# main_xml.net
KiCad netlist of a schematic drawn in EAGLE
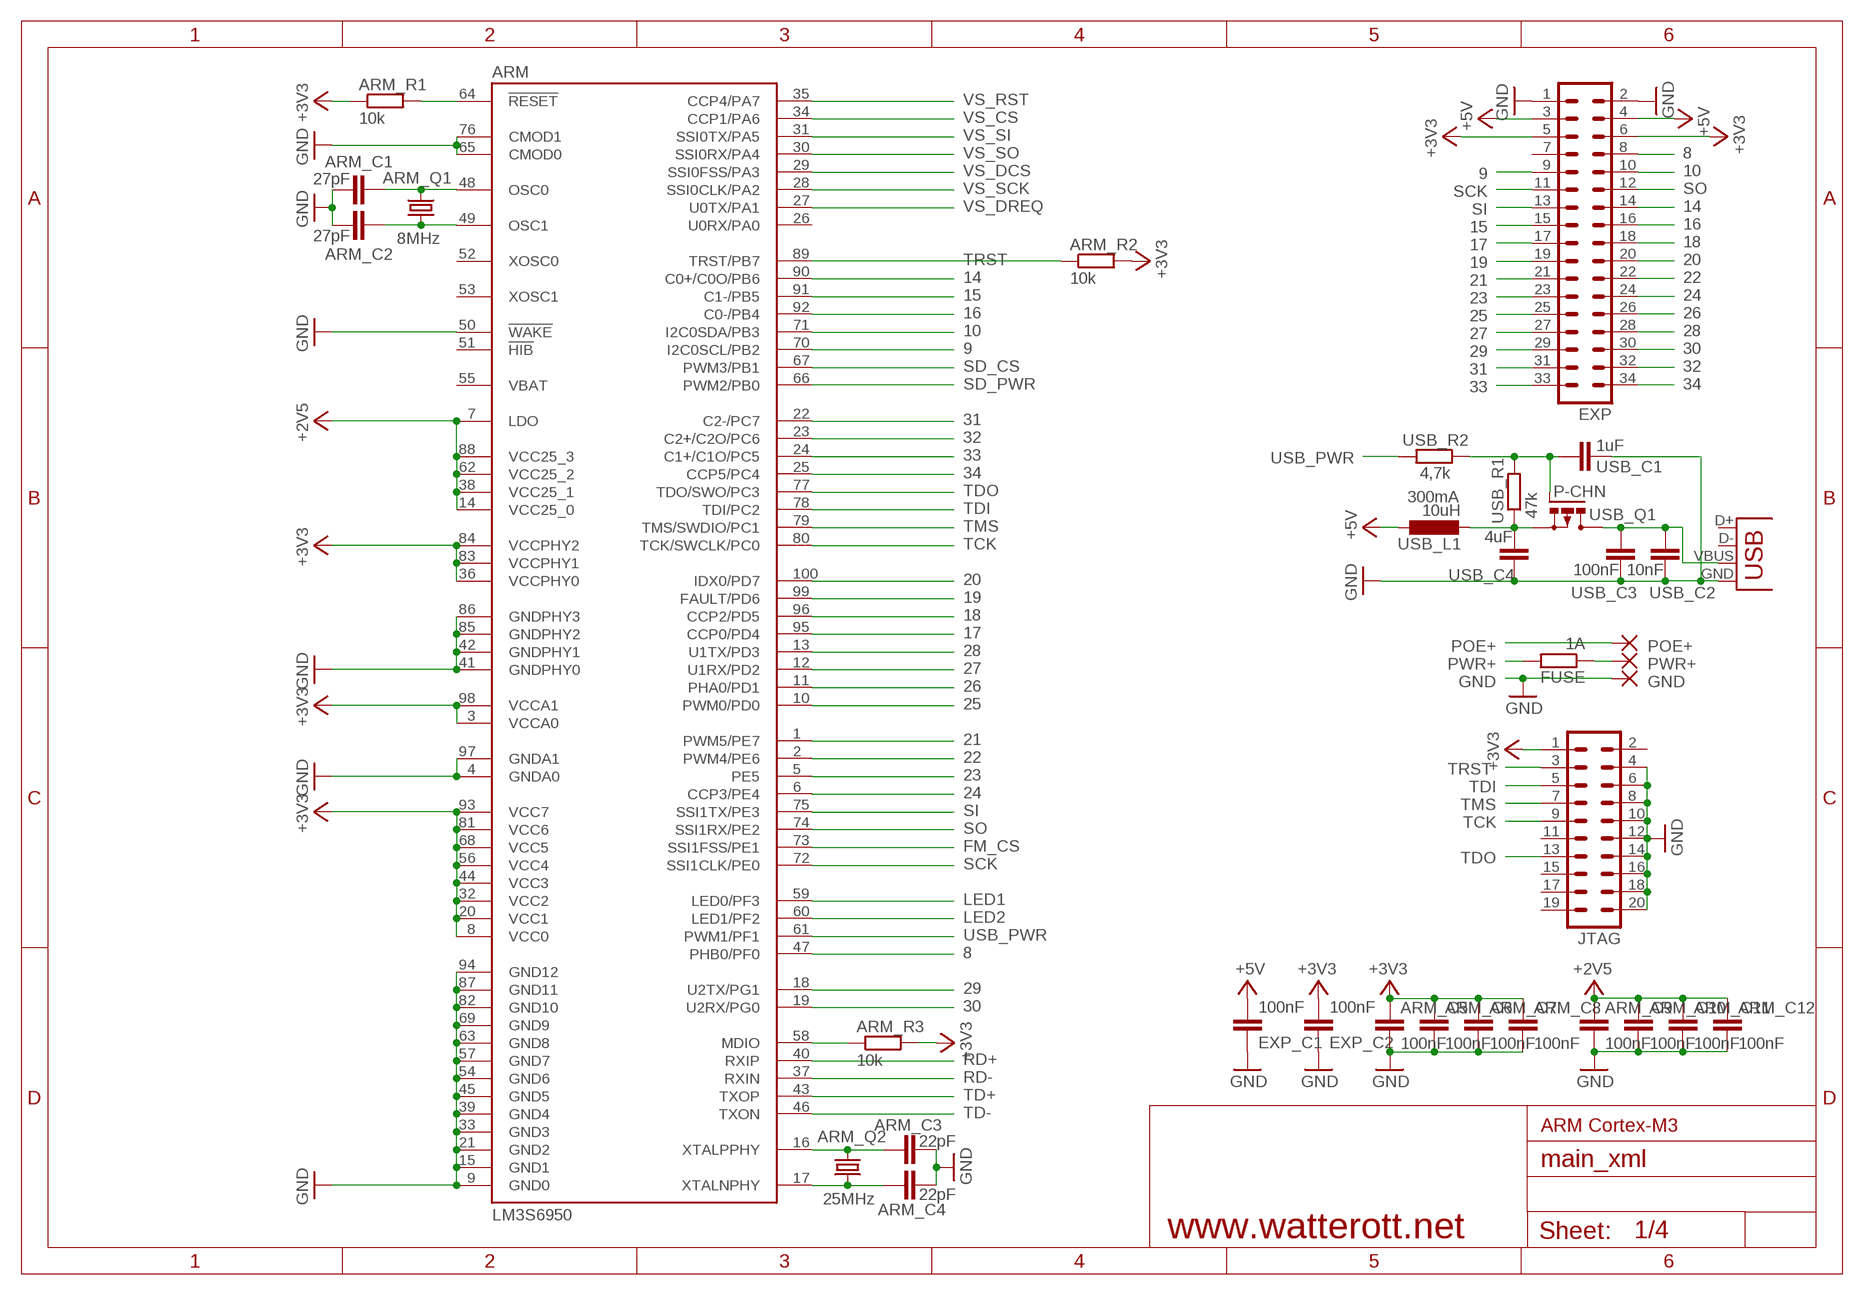
[diagram p0: schematic, sheet 1]
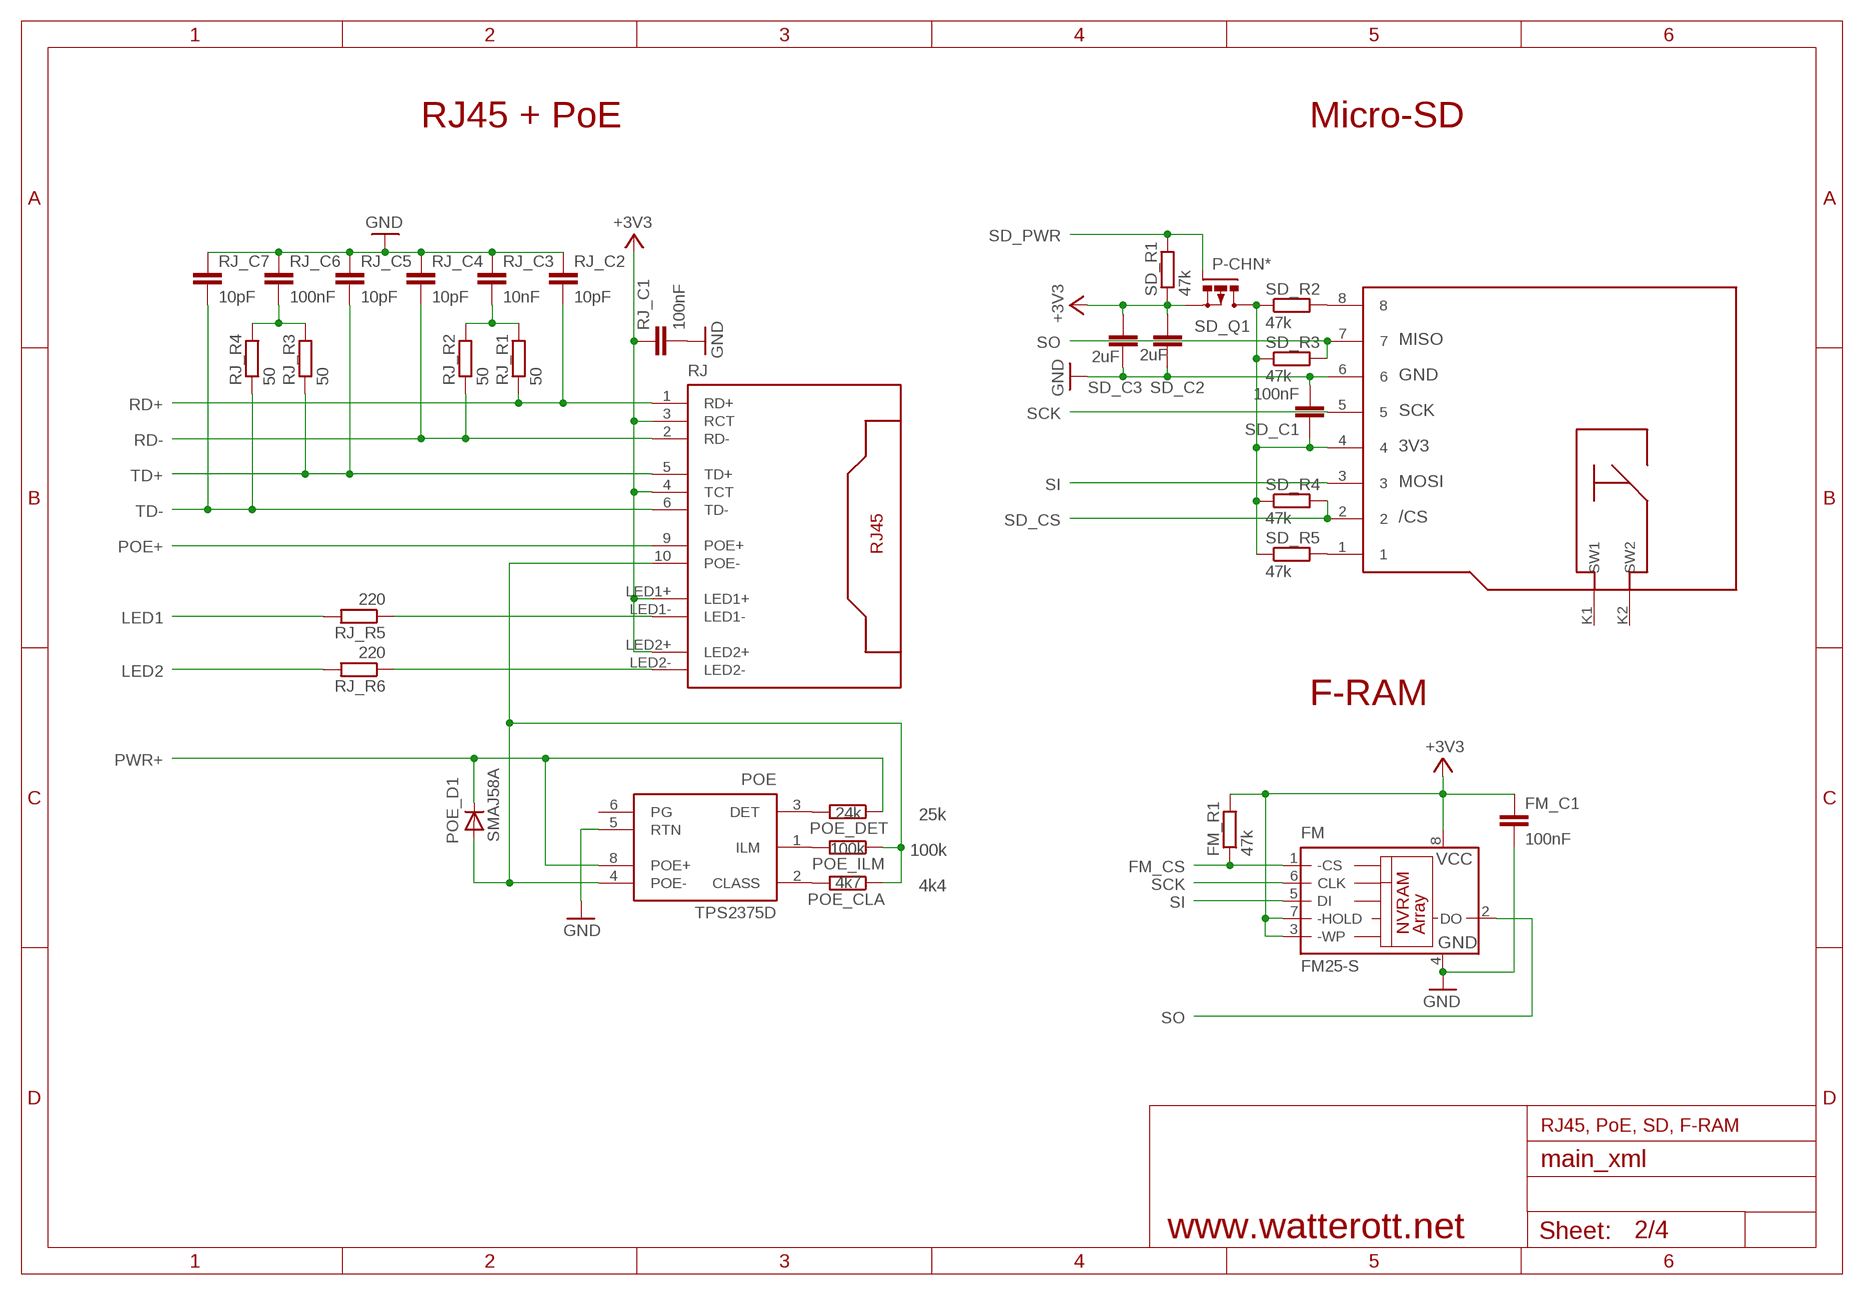
[diagram p1: schematic, sheet 2]
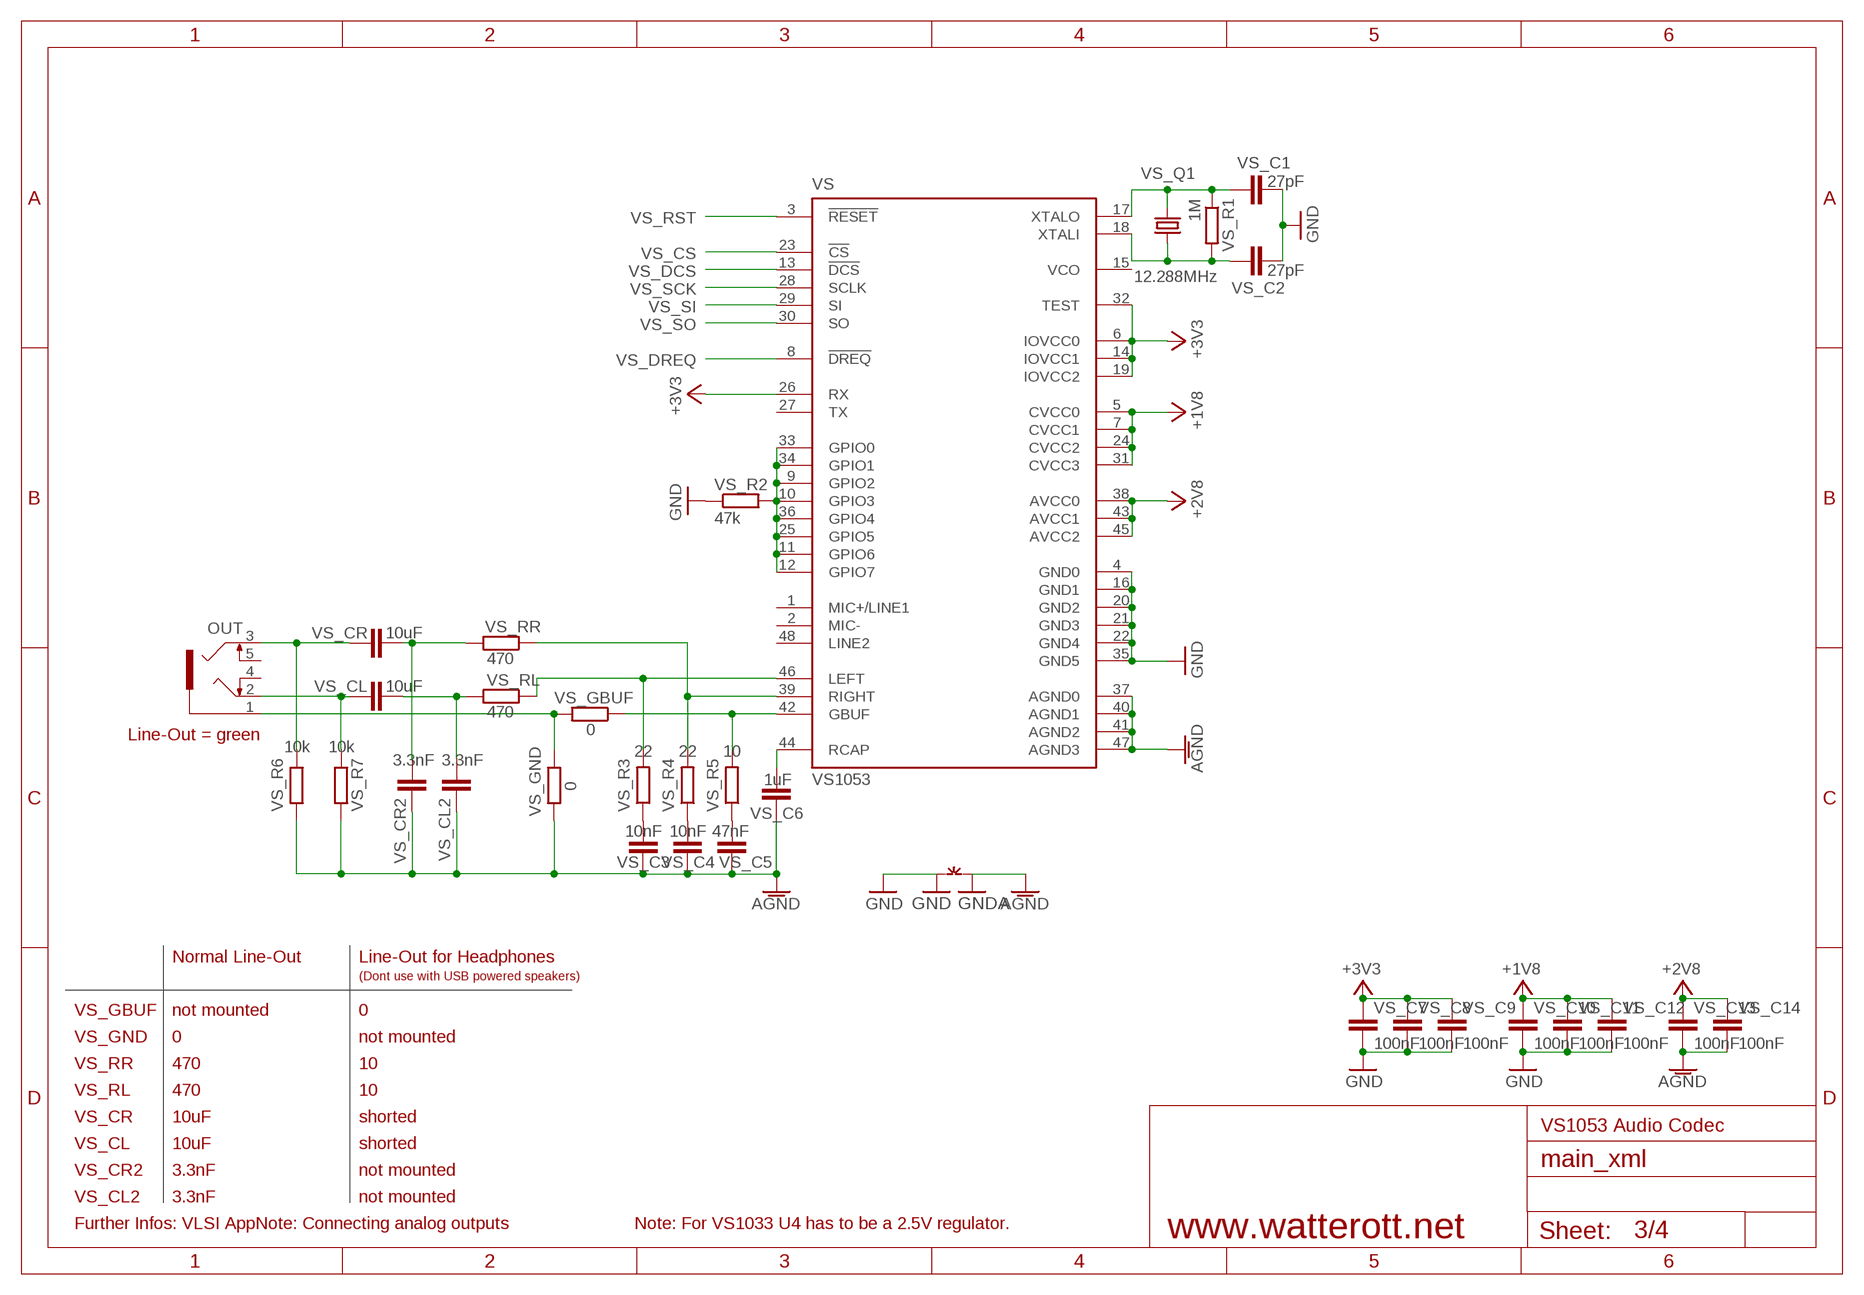
[diagram p2: schematic, sheet 3]
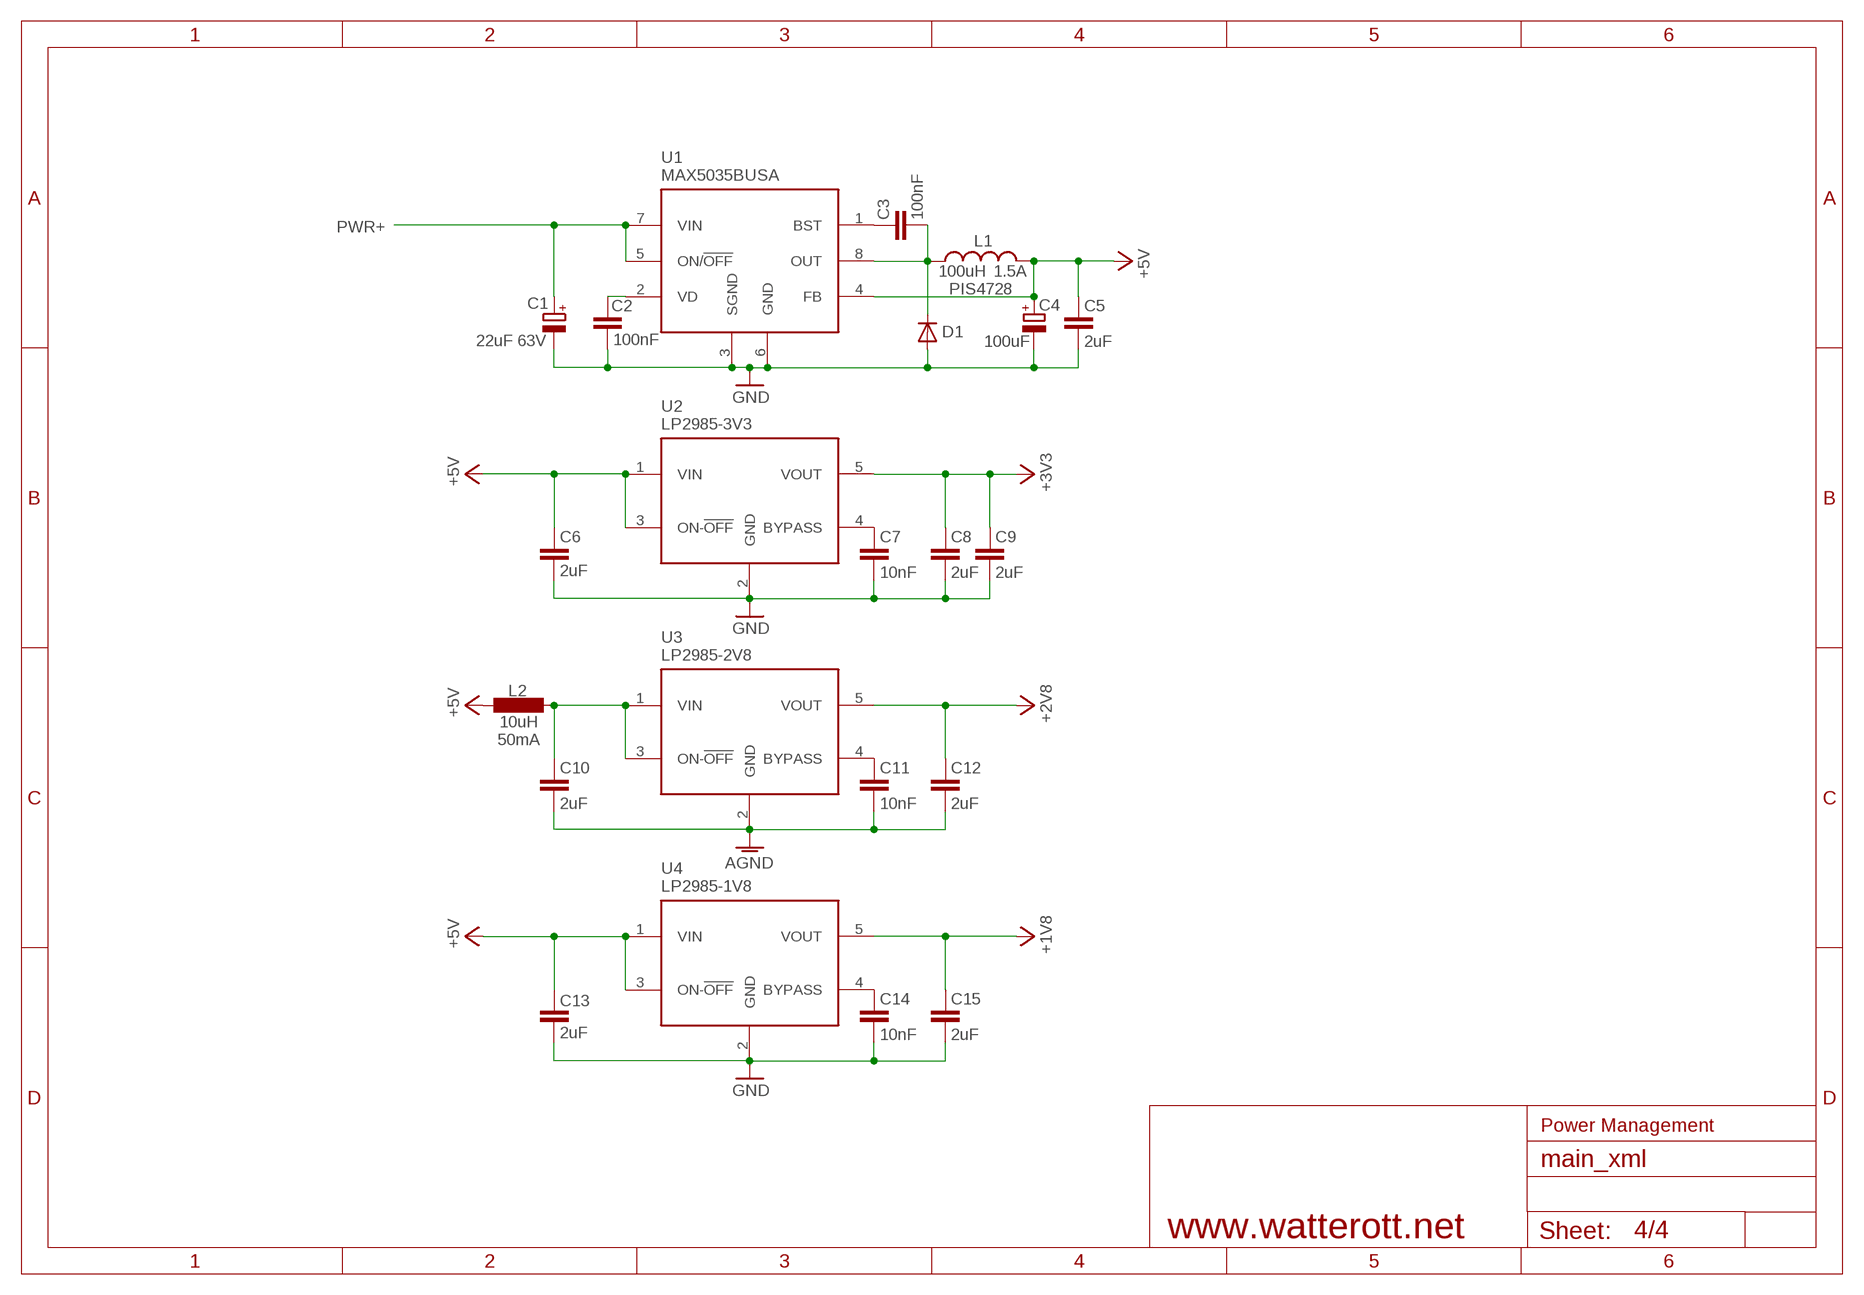
[diagram p3: schematic, sheet 4]

(export (version "E")
  (design (tool "Eeschema 10.0.6"))
  (components
    (comp (ref "FM")
      (value "FM25-S")
      (footprint "eagle-import:SO8")
      (libsource (lib "eagle-import") (part "FM25-S"))
    )
    (comp (ref "FM_C1")
      (value "100nF")
      (footprint "eagle-import:C0603")
      (libsource (lib "eagle-import") (part "C-EUC0603"))
    )
    (comp (ref "FM_R1")
      (value "47k")
      (footprint "eagle-import:R0603")
      (libsource (lib "eagle-import") (part "R-EU_R0603"))
    )
    (comp (ref "POE")
      (value "TPS2375D")
      (footprint "eagle-import:SO08")
      (libsource (lib "eagle-import") (part "TPS237X"))
    )
    (comp (ref "POE_CLA")
      (value "4k7")
      (footprint "eagle-import:R0603")
      (libsource (lib "eagle-import") (part "R-EU_R0603"))
    )
    (comp (ref "POE_D1")
      (value "SMAJ58A")
      (footprint "eagle-import:DO214AA")
      (libsource (lib "eagle-import") (part "DIODE-DO214AA"))
    )
    (comp (ref "POE_DET")
      (value "24k")
      (footprint "eagle-import:R0603")
      (libsource (lib "eagle-import") (part "R-EU_R0603"))
    )
    (comp (ref "POE_ILM")
      (value "100k")
      (footprint "eagle-import:R0603")
      (libsource (lib "eagle-import") (part "R-EU_R0603"))
    )
    (comp (ref "RJ")
      (value "RJ45-8-POEWE")
      (footprint "eagle-import:WE_POE")
      (libsource (lib "eagle-import") (part "RJ45-8-POEWE"))
    )
    (comp (ref "RJ_C1")
      (value "100nF")
      (footprint "eagle-import:C0603")
      (libsource (lib "eagle-import") (part "C-EUC0603"))
    )
    (comp (ref "RJ_C2")
      (value "10pF")
      (footprint "eagle-import:C0603")
      (libsource (lib "eagle-import") (part "C-EUC0603"))
    )
    (comp (ref "RJ_C3")
      (value "10nF")
      (footprint "eagle-import:C0603")
      (libsource (lib "eagle-import") (part "C-EUC0603"))
    )
    (comp (ref "RJ_C4")
      (value "10pF")
      (footprint "eagle-import:C0603")
      (libsource (lib "eagle-import") (part "C-EUC0603"))
    )
    (comp (ref "RJ_C5")
      (value "10pF")
      (footprint "eagle-import:C0603")
      (libsource (lib "eagle-import") (part "C-EUC0603"))
    )
    (comp (ref "RJ_C6")
      (value "100nF")
      (footprint "eagle-import:C0603")
      (libsource (lib "eagle-import") (part "C-EUC0603"))
    )
    (comp (ref "RJ_C7")
      (value "10pF")
      (footprint "eagle-import:C0603")
      (libsource (lib "eagle-import") (part "C-EUC0603"))
    )
    (comp (ref "RJ_R1")
      (value "50")
      (footprint "eagle-import:R0603")
      (libsource (lib "eagle-import") (part "R-EU_R0603"))
    )
    (comp (ref "RJ_R2")
      (value "50")
      (footprint "eagle-import:R0603")
      (libsource (lib "eagle-import") (part "R-EU_R0603"))
    )
    (comp (ref "RJ_R3")
      (value "50")
      (footprint "eagle-import:R0603")
      (libsource (lib "eagle-import") (part "R-EU_R0603"))
    )
    (comp (ref "RJ_R4")
      (value "50")
      (footprint "eagle-import:R0603")
      (libsource (lib "eagle-import") (part "R-EU_R0603"))
    )
    (comp (ref "RJ_R5")
      (value "220")
      (footprint "eagle-import:R0603")
      (libsource (lib "eagle-import") (part "R-EU_R0603"))
    )
    (comp (ref "RJ_R6")
      (value "220")
      (footprint "eagle-import:R0603")
      (libsource (lib "eagle-import") (part "R-EU_R0603"))
    )
    (comp (ref "SD")
      (value "MICRO-SD")
      (footprint "eagle-import:MICRO-SD")
      (libsource (lib "eagle-import") (part "MICRO-SD"))
    )
    (comp (ref "SD_C1")
      (value "100nF")
      (footprint "eagle-import:C0603")
      (libsource (lib "eagle-import") (part "C-EUC0603"))
    )
    (comp (ref "SD_C2")
      (value "2uF")
      (footprint "eagle-import:C0603")
      (libsource (lib "eagle-import") (part "C-EUC0603"))
    )
    (comp (ref "SD_C3")
      (value "2uF")
      (footprint "eagle-import:C0805")
      (libsource (lib "eagle-import") (part "C-EUC0805"))
    )
    (comp (ref "SD_Q1")
      (value "P-CHN*")
      (footprint "eagle-import:MICRO3")
      (libsource (lib "eagle-import") (part "IRLML6402"))
    )
    (comp (ref "SD_R1")
      (value "47k")
      (footprint "eagle-import:R0603")
      (libsource (lib "eagle-import") (part "R-EU_R0603"))
    )
    (comp (ref "SD_R2")
      (value "47k")
      (footprint "eagle-import:R0603")
      (libsource (lib "eagle-import") (part "R-EU_R0603"))
    )
    (comp (ref "SD_R3")
      (value "47k")
      (footprint "eagle-import:R0603")
      (libsource (lib "eagle-import") (part "R-EU_R0603"))
    )
    (comp (ref "SD_R4")
      (value "47k")
      (footprint "eagle-import:R0603")
      (libsource (lib "eagle-import") (part "R-EU_R0603"))
    )
    (comp (ref "SD_R5")
      (value "47k")
      (footprint "eagle-import:R0603")
      (libsource (lib "eagle-import") (part "R-EU_R0603"))
    )
    (comp (ref "ARM")
      (value "LM3S6950")
      (footprint "eagle-import:LQFP100")
      (libsource (lib "eagle-import") (part "LM3S6950"))
    )
    (comp (ref "ARM_C1")
      (value "27pF")
      (footprint "eagle-import:C0603")
      (libsource (lib "eagle-import") (part "C-EUC0603"))
    )
    (comp (ref "ARM_C2")
      (value "27pF")
      (footprint "eagle-import:C0603")
      (libsource (lib "eagle-import") (part "C-EUC0603"))
    )
    (comp (ref "ARM_C3")
      (value "22pF")
      (footprint "eagle-import:C0603")
      (libsource (lib "eagle-import") (part "C-EUC0603"))
    )
    (comp (ref "ARM_C4")
      (value "22pF")
      (footprint "eagle-import:C0603")
      (libsource (lib "eagle-import") (part "C-EUC0603"))
    )
    (comp (ref "ARM_C5")
      (value "100nF")
      (footprint "eagle-import:C0603")
      (libsource (lib "eagle-import") (part "C-EUC0603"))
    )
    (comp (ref "ARM_C6")
      (value "100nF")
      (footprint "eagle-import:C0603")
      (libsource (lib "eagle-import") (part "C-EUC0603"))
    )
    (comp (ref "ARM_C7")
      (value "100nF")
      (footprint "eagle-import:C0603")
      (libsource (lib "eagle-import") (part "C-EUC0603"))
    )
    (comp (ref "ARM_C8")
      (value "100nF")
      (footprint "eagle-import:C0603")
      (libsource (lib "eagle-import") (part "C-EUC0603"))
    )
    (comp (ref "ARM_C9")
      (value "100nF")
      (footprint "eagle-import:C0603")
      (libsource (lib "eagle-import") (part "C-EUC0603"))
    )
    (comp (ref "ARM_C10")
      (value "100nF")
      (footprint "eagle-import:C0603")
      (libsource (lib "eagle-import") (part "C-EUC0603"))
    )
    (comp (ref "ARM_C11")
      (value "100nF")
      (footprint "eagle-import:C0603")
      (libsource (lib "eagle-import") (part "C-EUC0603"))
    )
    (comp (ref "ARM_C12")
      (value "100nF")
      (footprint "eagle-import:C0603")
      (libsource (lib "eagle-import") (part "C-EUC0603"))
    )
    (comp (ref "ARM_Q1")
      (value "8MHz")
      (footprint "eagle-import:HC49UP")
      (libsource (lib "eagle-import") (part "HC49UP"))
    )
    (comp (ref "ARM_Q2")
      (value "25MHz")
      (footprint "eagle-import:HC49UP")
      (libsource (lib "eagle-import") (part "HC49UP"))
    )
    (comp (ref "ARM_R1")
      (value "10k")
      (footprint "eagle-import:R0603")
      (libsource (lib "eagle-import") (part "R-EU_R0603"))
    )
    (comp (ref "ARM_R2")
      (value "10k")
      (footprint "eagle-import:R0603")
      (libsource (lib "eagle-import") (part "R-EU_R0603"))
    )
    (comp (ref "ARM_R3")
      (value "10k")
      (footprint "eagle-import:R0603")
      (libsource (lib "eagle-import") (part "R-EU_R0603"))
    )
    (comp (ref "EXP")
      (value "MA17-2")
      (footprint "eagle-import:MA17-2")
      (libsource (lib "eagle-import") (part "MA17-2"))
    )
    (comp (ref "EXP_C1")
      (value "100nF")
      (footprint "eagle-import:C0603")
      (libsource (lib "eagle-import") (part "C-EUC0603"))
    )
    (comp (ref "EXP_C2")
      (value "100nF")
      (footprint "eagle-import:C0603")
      (libsource (lib "eagle-import") (part "C-EUC0603"))
    )
    (comp (ref "FUSE")
      (value "1A")
      (footprint "eagle-import:R1206")
      (libsource (lib "eagle-import") (part "R-EU_R1206"))
    )
    (comp (ref "GND")
      (value "SMD2")
      (footprint "eagle-import:SMD1,27-2,54")
      (libsource (lib "eagle-import") (part "SMD2"))
    )
    (comp (ref "JTAG")
      (value "MA10-2")
      (footprint "eagle-import:MA10-2")
      (libsource (lib "eagle-import") (part "MA10-2"))
    )
    (comp (ref "POE+")
      (value "SMD2")
      (footprint "eagle-import:SMD1,27-2,54")
      (libsource (lib "eagle-import") (part "SMD2"))
    )
    (comp (ref "PWR+")
      (value "SMD2")
      (footprint "eagle-import:SMD1,27-2,54")
      (libsource (lib "eagle-import") (part "SMD2"))
    )
    (comp (ref "USB")
      (value "USB-A-S")
      (footprint "eagle-import:USB-A-S")
      (libsource (lib "eagle-import") (part "USB-A-S"))
    )
    (comp (ref "USB_C1")
      (value "1uF")
      (footprint "eagle-import:C0603")
      (libsource (lib "eagle-import") (part "C-EUC0603"))
    )
    (comp (ref "USB_C2")
      (value "10nF")
      (footprint "eagle-import:C0603")
      (libsource (lib "eagle-import") (part "C-EUC0603"))
    )
    (comp (ref "USB_C3")
      (value "100nF")
      (footprint "eagle-import:C0603")
      (libsource (lib "eagle-import") (part "C-EUC0603"))
    )
    (comp (ref "USB_C4")
      (value "4uF")
      (footprint "eagle-import:C1206")
      (libsource (lib "eagle-import") (part "C-EUC1206"))
    )
    (comp (ref "USB_L1")
      (value "10uH")
      (footprint "eagle-import:L4532M")
      (libsource (lib "eagle-import") (part "L-EUL4532C"))
    )
    (comp (ref "USB_Q1")
      (value "P-CHN")
      (footprint "eagle-import:MICRO3")
      (libsource (lib "eagle-import") (part "IRLML6402"))
    )
    (comp (ref "USB_R1")
      (value "47k")
      (footprint "eagle-import:R0603")
      (libsource (lib "eagle-import") (part "R-EU_R0603"))
    )
    (comp (ref "USB_R2")
      (value "4,7k")
      (footprint "eagle-import:R0603")
      (libsource (lib "eagle-import") (part "R-EU_R0603"))
    )
    (comp (ref "C1")
      (value "22uF 63V")
      (footprint "eagle-import:153CLV-0810")
      (libsource (lib "eagle-import") (part "CPOL-EU153CLV-0810"))
    )
    (comp (ref "C2")
      (value "100nF")
      (footprint "eagle-import:C0603")
      (libsource (lib "eagle-import") (part "C-EUC0603"))
    )
    (comp (ref "C3")
      (value "100nF")
      (footprint "eagle-import:C0603")
      (libsource (lib "eagle-import") (part "C-EUC0603"))
    )
    (comp (ref "C4")
      (value "100uF")
      (footprint "eagle-import:153CLV-0810")
      (libsource (lib "eagle-import") (part "CPOL-EU153CLV-0810"))
    )
    (comp (ref "C5")
      (value "2uF")
      (footprint "eagle-import:C0603")
      (libsource (lib "eagle-import") (part "C-EUC0603"))
    )
    (comp (ref "C6")
      (value "2uF")
      (footprint "eagle-import:C0603")
      (libsource (lib "eagle-import") (part "C-EUC0603"))
    )
    (comp (ref "C7")
      (value "10nF")
      (footprint "eagle-import:C0603")
      (libsource (lib "eagle-import") (part "C-EUC0603"))
    )
    (comp (ref "C8")
      (value "2uF")
      (footprint "eagle-import:C0603")
      (libsource (lib "eagle-import") (part "C-EUC0603"))
    )
    (comp (ref "C9")
      (value "2uF")
      (footprint "eagle-import:C0603")
      (libsource (lib "eagle-import") (part "C-EUC0603"))
    )
    (comp (ref "C10")
      (value "2uF")
      (footprint "eagle-import:C0603")
      (libsource (lib "eagle-import") (part "C-EUC0603"))
    )
    (comp (ref "C11")
      (value "10nF")
      (footprint "eagle-import:C0603")
      (libsource (lib "eagle-import") (part "C-EUC0603"))
    )
    (comp (ref "C12")
      (value "2uF")
      (footprint "eagle-import:C0603")
      (libsource (lib "eagle-import") (part "C-EUC0603"))
    )
    (comp (ref "C13")
      (value "2uF")
      (footprint "eagle-import:C0603")
      (libsource (lib "eagle-import") (part "C-EUC0603"))
    )
    (comp (ref "C14")
      (value "10nF")
      (footprint "eagle-import:C0603")
      (libsource (lib "eagle-import") (part "C-EUC0603"))
    )
    (comp (ref "C15")
      (value "2uF")
      (footprint "eagle-import:C0603")
      (libsource (lib "eagle-import") (part "C-EUC0603"))
    )
    (comp (ref "D1")
      (value "Schottky 90V")
      (footprint "eagle-import:DO214AA")
      (libsource (lib "eagle-import") (part "DIODE-DO214AA"))
    )
    (comp (ref "L1")
      (value "100uH")
      (footprint "eagle-import:CDRH")
      (libsource (lib "eagle-import") (part "INDUCTORCDRH"))
    )
    (comp (ref "L2")
      (value "10uH")
      (footprint "eagle-import:L3216C")
      (libsource (lib "eagle-import") (part "L-EUL3216C"))
    )
    (comp (ref "U1")
      (value "MAX5035BUSA")
      (footprint "eagle-import:SO8")
      (libsource (lib "eagle-import") (part "MAX5035"))
    )
    (comp (ref "U2")
      (value "LP2985-3V3")
      (footprint "eagle-import:SOT23-5")
      (libsource (lib "eagle-import") (part "LP2985"))
    )
    (comp (ref "U3")
      (value "LP2985-2V8")
      (footprint "eagle-import:SOT23-5")
      (libsource (lib "eagle-import") (part "LP2985"))
    )
    (comp (ref "U4")
      (value "LP2985-1V8")
      (footprint "eagle-import:SOT23-5")
      (libsource (lib "eagle-import") (part "LP2985"))
    )
    (comp (ref "OUT")
      (value "1503_09")
      (footprint "eagle-import:1503_09")
      (libsource (lib "eagle-import") (part "1503_09"))
    )
    (comp (ref "VS")
      (value "VS1053")
      (footprint "eagle-import:LQFP-48")
      (libsource (lib "eagle-import") (part "VS1053"))
    )
    (comp (ref "VS_C1")
      (value "27pF")
      (footprint "eagle-import:C0603")
      (libsource (lib "eagle-import") (part "C-EUC0603"))
    )
    (comp (ref "VS_C2")
      (value "27pF")
      (footprint "eagle-import:C0603")
      (libsource (lib "eagle-import") (part "C-EUC0603"))
    )
    (comp (ref "VS_C3")
      (value "10nF")
      (footprint "eagle-import:C0603")
      (libsource (lib "eagle-import") (part "C-EUC0603"))
    )
    (comp (ref "VS_C4")
      (value "10nF")
      (footprint "eagle-import:C0603")
      (libsource (lib "eagle-import") (part "C-EUC0603"))
    )
    (comp (ref "VS_C5")
      (value "47nF")
      (footprint "eagle-import:C0603")
      (libsource (lib "eagle-import") (part "C-EUC0603"))
    )
    (comp (ref "VS_C6")
      (value "1uF")
      (footprint "eagle-import:C0603")
      (libsource (lib "eagle-import") (part "C-EUC0603"))
    )
    (comp (ref "VS_C7")
      (value "100nF")
      (footprint "eagle-import:C0603")
      (libsource (lib "eagle-import") (part "C-EUC0603"))
    )
    (comp (ref "VS_C8")
      (value "100nF")
      (footprint "eagle-import:C0603")
      (libsource (lib "eagle-import") (part "C-EUC0603"))
    )
    (comp (ref "VS_C9")
      (value "100nF")
      (footprint "eagle-import:C0603")
      (libsource (lib "eagle-import") (part "C-EUC0603"))
    )
    (comp (ref "VS_C10")
      (value "100nF")
      (footprint "eagle-import:C0603")
      (libsource (lib "eagle-import") (part "C-EUC0603"))
    )
    (comp (ref "VS_C11")
      (value "100nF")
      (footprint "eagle-import:C0603")
      (libsource (lib "eagle-import") (part "C-EUC0603"))
    )
    (comp (ref "VS_C12")
      (value "100nF")
      (footprint "eagle-import:C0603")
      (libsource (lib "eagle-import") (part "C-EUC0603"))
    )
    (comp (ref "VS_C13")
      (value "100nF")
      (footprint "eagle-import:C0603")
      (libsource (lib "eagle-import") (part "C-EUC0603"))
    )
    (comp (ref "VS_C14")
      (value "100nF")
      (footprint "eagle-import:C0603")
      (libsource (lib "eagle-import") (part "C-EUC0603"))
    )
    (comp (ref "VS_CL")
      (value "10uF")
      (footprint "eagle-import:C1812")
      (libsource (lib "eagle-import") (part "C-EUC1812"))
    )
    (comp (ref "VS_CL2")
      (value "3.3nF")
      (footprint "eagle-import:C0603")
      (libsource (lib "eagle-import") (part "C-EUC0603"))
    )
    (comp (ref "VS_CR")
      (value "10uF")
      (footprint "eagle-import:C1812")
      (libsource (lib "eagle-import") (part "C-EUC1812"))
    )
    (comp (ref "VS_CR2")
      (value "3.3nF")
      (footprint "eagle-import:C0603")
      (libsource (lib "eagle-import") (part "C-EUC0603"))
    )
    (comp (ref "VS_GBUF")
      (value "0")
      (footprint "eagle-import:R0603")
      (libsource (lib "eagle-import") (part "R-EU_R0603"))
    )
    (comp (ref "VS_GND")
      (value "0")
      (footprint "eagle-import:R0603")
      (libsource (lib "eagle-import") (part "R-EU_R0603"))
    )
    (comp (ref "VS_Q1")
      (value "12.288MHz")
      (footprint "eagle-import:HC49UP")
      (libsource (lib "eagle-import") (part "HC49UP"))
    )
    (comp (ref "VS_R1")
      (value "1M")
      (footprint "eagle-import:R0603")
      (libsource (lib "eagle-import") (part "R-EU_R0603"))
    )
    (comp (ref "VS_R2")
      (value "47k")
      (footprint "eagle-import:R0603")
      (libsource (lib "eagle-import") (part "R-EU_R0603"))
    )
    (comp (ref "VS_R3")
      (value "22")
      (footprint "eagle-import:R0603")
      (libsource (lib "eagle-import") (part "R-EU_R0603"))
    )
    (comp (ref "VS_R4")
      (value "22")
      (footprint "eagle-import:R0603")
      (libsource (lib "eagle-import") (part "R-EU_R0603"))
    )
    (comp (ref "VS_R5")
      (value "10")
      (footprint "eagle-import:R0603")
      (libsource (lib "eagle-import") (part "R-EU_R0603"))
    )
    (comp (ref "VS_R6")
      (value "10k")
      (footprint "eagle-import:R0603")
      (libsource (lib "eagle-import") (part "R-EU_R0603"))
    )
    (comp (ref "VS_R7")
      (value "10k")
      (footprint "eagle-import:R0603")
      (libsource (lib "eagle-import") (part "R-EU_R0603"))
    )
    (comp (ref "VS_RL")
      (value "470")
      (footprint "eagle-import:R0603")
      (libsource (lib "eagle-import") (part "R-EU_R0603"))
    )
    (comp (ref "VS_RR")
      (value "470")
      (footprint "eagle-import:R0603")
      (libsource (lib "eagle-import") (part "R-EU_R0603"))
    )
    (comp (ref "~NUDEV~1")
      (value "GND-GNDA")
      (footprint "eagle-import:GND-GNDA")
      (libsource (lib "eagle-import") (part "GND-GNDA"))
    )
  )
  (nets
    (net (code "1") (name "+1V8") (class "Default")
      (node (ref "C15") (pin "1") (pinfunction "1_1") (pintype "passive"))
      (node (ref "U4") (pin "5") (pinfunction "VOUT_5") (pintype "power_in"))
      (node (ref "VS") (pin "24") (pinfunction "CVCC2_24") (pintype "power_in"))
      (node (ref "VS") (pin "31") (pinfunction "CVCC3_31") (pintype "power_in"))
      (node (ref "VS") (pin "5") (pinfunction "CVCC0_5") (pintype "power_in"))
      (node (ref "VS") (pin "7") (pinfunction "CVCC1_7") (pintype "power_in"))
      (node (ref "VS_C10") (pin "1") (pinfunction "1_1") (pintype "passive"))
      (node (ref "VS_C11") (pin "1") (pinfunction "1_1") (pintype "passive"))
      (node (ref "VS_C12") (pin "1") (pinfunction "1_1") (pintype "passive"))
    )
    (net (code "2") (name "+2V8") (class "Default")
      (node (ref "C12") (pin "1") (pinfunction "1_1") (pintype "passive"))
      (node (ref "U3") (pin "5") (pinfunction "VOUT_5") (pintype "power_in"))
      (node (ref "VS") (pin "38") (pinfunction "AVCC0_38") (pintype "power_in"))
      (node (ref "VS") (pin "43") (pinfunction "AVCC1_43") (pintype "power_in"))
      (node (ref "VS") (pin "45") (pinfunction "AVCC2_45") (pintype "power_in"))
      (node (ref "VS_C13") (pin "1") (pinfunction "1_1") (pintype "passive"))
      (node (ref "VS_C14") (pin "1") (pinfunction "1_1") (pintype "passive"))
    )
    (net (code "3") (name "+3V3") (class "Default")
      (node (ref "ARM") (pin "20") (pinfunction "VCC1_20") (pintype "power_in"))
      (node (ref "ARM") (pin "3") (pinfunction "VCCA0_3") (pintype "power_in"))
      (node (ref "ARM") (pin "32") (pinfunction "VCC2_32") (pintype "power_in"))
      (node (ref "ARM") (pin "36") (pinfunction "VCCPHY0_36") (pintype "power_in"))
      (node (ref "ARM") (pin "44") (pinfunction "VCC3_44") (pintype "power_in"))
      (node (ref "ARM") (pin "56") (pinfunction "VCC4_56") (pintype "power_in"))
      (node (ref "ARM") (pin "68") (pinfunction "VCC5_68") (pintype "power_in"))
      (node (ref "ARM") (pin "8") (pinfunction "VCC0_8") (pintype "power_in"))
      (node (ref "ARM") (pin "81") (pinfunction "VCC6_81") (pintype "power_in"))
      (node (ref "ARM") (pin "83") (pinfunction "VCCPHY1_83") (pintype "power_in"))
      (node (ref "ARM") (pin "84") (pinfunction "VCCPHY2_84") (pintype "power_in"))
      (node (ref "ARM") (pin "93") (pinfunction "VCC7_93") (pintype "power_in"))
      (node (ref "ARM") (pin "98") (pinfunction "VCCA1_98") (pintype "power_in"))
      (node (ref "ARM_C5") (pin "1") (pinfunction "1_1") (pintype "passive"))
      (node (ref "ARM_C6") (pin "1") (pinfunction "1_1") (pintype "passive"))
      (node (ref "ARM_C7") (pin "1") (pinfunction "1_1") (pintype "passive"))
      (node (ref "ARM_C8") (pin "1") (pinfunction "1_1") (pintype "passive"))
      (node (ref "ARM_R1") (pin "1") (pinfunction "1_1") (pintype "passive"))
      (node (ref "ARM_R2") (pin "2") (pinfunction "2_2") (pintype "passive"))
      (node (ref "ARM_R3") (pin "2") (pinfunction "2_2") (pintype "passive"))
      (node (ref "C8") (pin "1") (pinfunction "1_1") (pintype "passive"))
      (node (ref "C9") (pin "1") (pinfunction "1_1") (pintype "passive"))
      (node (ref "EXP") (pin "5") (pinfunction "5_5") (pintype "passive"))
      (node (ref "EXP") (pin "6") (pinfunction "6_6") (pintype "passive"))
      (node (ref "EXP_C2") (pin "2") (pinfunction "2_2") (pintype "passive"))
      (node (ref "FM") (pin "3") (pinfunction "-WP_3") (pintype "input"))
      (node (ref "FM") (pin "7") (pinfunction "-HOLD_7") (pintype "input"))
      (node (ref "FM") (pin "8") (pinfunction "VCC_8") (pintype "power_in"))
      (node (ref "FM_C1") (pin "1") (pinfunction "1_1") (pintype "passive"))
      (node (ref "FM_R1") (pin "2") (pinfunction "2_2") (pintype "passive"))
      (node (ref "JTAG") (pin "1") (pinfunction "1_1") (pintype "passive"))
      (node (ref "RJ") (pin "3") (pinfunction "RCT_3") (pintype "bidirectional"))
      (node (ref "RJ") (pin "4") (pinfunction "TCT_4") (pintype "bidirectional"))
      (node (ref "RJ") (pin "LED1+") (pinfunction "LED1+_LED1+") (pintype "input"))
      (node (ref "RJ") (pin "LED2+") (pinfunction "LED2+_LED2+") (pintype "input"))
      (node (ref "RJ_C1") (pin "1") (pinfunction "1_1") (pintype "passive"))
      (node (ref "SD_C2") (pin "2") (pinfunction "2_2") (pintype "passive"))
      (node (ref "SD_C3") (pin "2") (pinfunction "2_2") (pintype "passive"))
      (node (ref "SD_Q1") (pin "2") (pinfunction "S_2") (pintype "passive"))
      (node (ref "SD_R1") (pin "1") (pinfunction "1_1") (pintype "passive"))
      (node (ref "U2") (pin "5") (pinfunction "VOUT_5") (pintype "power_in"))
      (node (ref "VS") (pin "14") (pinfunction "IOVCC1_14") (pintype "power_in"))
      (node (ref "VS") (pin "19") (pinfunction "IOVCC2_19") (pintype "power_in"))
      (node (ref "VS") (pin "26") (pinfunction "RX_26") (pintype "input"))
      (node (ref "VS") (pin "32") (pinfunction "TEST_32") (pintype "input"))
      (node (ref "VS") (pin "6") (pinfunction "IOVCC0_6") (pintype "power_in"))
      (node (ref "VS_C7") (pin "1") (pinfunction "1_1") (pintype "passive"))
      (node (ref "VS_C8") (pin "1") (pinfunction "1_1") (pintype "passive"))
      (node (ref "VS_C9") (pin "1") (pinfunction "1_1") (pintype "passive"))
    )
    (net (code "4") (name "+5V") (class "Default")
      (node (ref "C13") (pin "2") (pinfunction "2_2") (pintype "passive"))
      (node (ref "C4") (pin "+") (pinfunction "+_+") (pintype "passive"))
      (node (ref "C5") (pin "1") (pinfunction "1_1") (pintype "passive"))
      (node (ref "C6") (pin "2") (pinfunction "2_2") (pintype "passive"))
      (node (ref "EXP") (pin "3") (pinfunction "3_3") (pintype "passive"))
      (node (ref "EXP") (pin "4") (pinfunction "4_4") (pintype "passive"))
      (node (ref "EXP_C1") (pin "2") (pinfunction "2_2") (pintype "passive"))
      (node (ref "L1") (pin "2") (pinfunction "2_2") (pintype "passive"))
      (node (ref "L2") (pin "1") (pinfunction "1_1") (pintype "passive"))
      (node (ref "U1") (pin "4") (pinfunction "FB_4") (pintype "input"))
      (node (ref "U2") (pin "1") (pinfunction "VIN_1") (pintype "power_in"))
      (node (ref "U2") (pin "3") (pinfunction "ON-~{OFF}_3") (pintype "input"))
      (node (ref "U4") (pin "1") (pinfunction "VIN_1") (pintype "power_in"))
      (node (ref "U4") (pin "3") (pinfunction "ON-~{OFF}_3") (pintype "input"))
      (node (ref "USB_L1") (pin "1") (pinfunction "1_1") (pintype "passive"))
    )
    (net (code "5") (name "8") (class "Default")
      (node (ref "ARM") (pin "47") (pinfunction "PHB0/PF0_47") (pintype "bidirectional"))
      (node (ref "EXP") (pin "8") (pinfunction "8_8") (pintype "passive"))
    )
    (net (code "6") (name "9") (class "Default")
      (node (ref "ARM") (pin "70") (pinfunction "I2C0SCL/PB2_70") (pintype "bidirectional"))
      (node (ref "EXP") (pin "9") (pinfunction "9_9") (pintype "passive"))
    )
    (net (code "7") (name "10") (class "Default")
      (node (ref "ARM") (pin "71") (pinfunction "I2C0SDA/PB3_71") (pintype "bidirectional"))
      (node (ref "EXP") (pin "10") (pinfunction "10_10") (pintype "passive"))
    )
    (net (code "8") (name "14") (class "Default")
      (node (ref "ARM") (pin "90") (pinfunction "C0+/C0O/PB6_90") (pintype "bidirectional"))
      (node (ref "EXP") (pin "14") (pinfunction "14_14") (pintype "passive"))
    )
    (net (code "9") (name "15") (class "Default")
      (node (ref "ARM") (pin "91") (pinfunction "C1-/PB5_91") (pintype "bidirectional"))
      (node (ref "EXP") (pin "15") (pinfunction "15_15") (pintype "passive"))
    )
    (net (code "10") (name "16") (class "Default")
      (node (ref "ARM") (pin "92") (pinfunction "C0-/PB4_92") (pintype "bidirectional"))
      (node (ref "EXP") (pin "16") (pinfunction "16_16") (pintype "passive"))
    )
    (net (code "11") (name "17") (class "Default")
      (node (ref "ARM") (pin "95") (pinfunction "CCP0/PD4_95") (pintype "bidirectional"))
      (node (ref "EXP") (pin "17") (pinfunction "17_17") (pintype "passive"))
    )
    (net (code "12") (name "18") (class "Default")
      (node (ref "ARM") (pin "96") (pinfunction "CCP2/PD5_96") (pintype "bidirectional"))
      (node (ref "EXP") (pin "18") (pinfunction "18_18") (pintype "passive"))
    )
    (net (code "13") (name "19") (class "Default")
      (node (ref "ARM") (pin "99") (pinfunction "FAULT/PD6_99") (pintype "bidirectional"))
      (node (ref "EXP") (pin "19") (pinfunction "19_19") (pintype "passive"))
    )
    (net (code "14") (name "20") (class "Default")
      (node (ref "ARM") (pin "100") (pinfunction "IDX0/PD7_100") (pintype "bidirectional"))
      (node (ref "EXP") (pin "20") (pinfunction "20_20") (pintype "passive"))
    )
    (net (code "15") (name "21") (class "Default")
      (node (ref "ARM") (pin "1") (pinfunction "PWM5/PE7_1") (pintype "bidirectional"))
      (node (ref "EXP") (pin "21") (pinfunction "21_21") (pintype "passive"))
    )
    (net (code "16") (name "22") (class "Default")
      (node (ref "ARM") (pin "2") (pinfunction "PWM4/PE6_2") (pintype "bidirectional"))
      (node (ref "EXP") (pin "22") (pinfunction "22_22") (pintype "passive"))
    )
    (net (code "17") (name "23") (class "Default")
      (node (ref "ARM") (pin "5") (pinfunction "PE5_5") (pintype "bidirectional"))
      (node (ref "EXP") (pin "23") (pinfunction "23_23") (pintype "passive"))
    )
    (net (code "18") (name "24") (class "Default")
      (node (ref "ARM") (pin "6") (pinfunction "CCP3/PE4_6") (pintype "bidirectional"))
      (node (ref "EXP") (pin "24") (pinfunction "24_24") (pintype "passive"))
    )
    (net (code "19") (name "25") (class "Default")
      (node (ref "ARM") (pin "10") (pinfunction "PWM0/PD0_10") (pintype "bidirectional"))
      (node (ref "EXP") (pin "25") (pinfunction "25_25") (pintype "passive"))
    )
    (net (code "20") (name "26") (class "Default")
      (node (ref "ARM") (pin "11") (pinfunction "PHA0/PD1_11") (pintype "bidirectional"))
      (node (ref "EXP") (pin "26") (pinfunction "26_26") (pintype "passive"))
    )
    (net (code "21") (name "27") (class "Default")
      (node (ref "ARM") (pin "12") (pinfunction "U1RX/PD2_12") (pintype "bidirectional"))
      (node (ref "EXP") (pin "27") (pinfunction "27_27") (pintype "passive"))
    )
    (net (code "22") (name "28") (class "Default")
      (node (ref "ARM") (pin "13") (pinfunction "U1TX/PD3_13") (pintype "bidirectional"))
      (node (ref "EXP") (pin "28") (pinfunction "28_28") (pintype "passive"))
    )
    (net (code "23") (name "29") (class "Default")
      (node (ref "ARM") (pin "18") (pinfunction "U2TX/PG1_18") (pintype "bidirectional"))
      (node (ref "EXP") (pin "29") (pinfunction "29_29") (pintype "passive"))
    )
    (net (code "24") (name "30") (class "Default")
      (node (ref "ARM") (pin "19") (pinfunction "U2RX/PG0_19") (pintype "bidirectional"))
      (node (ref "EXP") (pin "30") (pinfunction "30_30") (pintype "passive"))
    )
    (net (code "25") (name "31") (class "Default")
      (node (ref "ARM") (pin "22") (pinfunction "C2-/PC7_22") (pintype "bidirectional"))
      (node (ref "EXP") (pin "31") (pinfunction "31_31") (pintype "passive"))
    )
    (net (code "26") (name "32") (class "Default")
      (node (ref "ARM") (pin "23") (pinfunction "C2+/C2O/PC6_23") (pintype "bidirectional"))
      (node (ref "EXP") (pin "32") (pinfunction "32_32") (pintype "passive"))
    )
    (net (code "27") (name "33") (class "Default")
      (node (ref "ARM") (pin "24") (pinfunction "C1+/C1O/PC5_24") (pintype "bidirectional"))
      (node (ref "EXP") (pin "33") (pinfunction "33_33") (pintype "passive"))
    )
    (net (code "28") (name "34") (class "Default")
      (node (ref "ARM") (pin "25") (pinfunction "CCP5/PC4_25") (pintype "bidirectional"))
      (node (ref "EXP") (pin "34") (pinfunction "34_34") (pintype "passive"))
    )
    (net (code "29") (name "AGND") (class "Default")
      (node (ref "C10") (pin "1") (pinfunction "1_1") (pintype "passive"))
      (node (ref "C11") (pin "2") (pinfunction "2_2") (pintype "passive"))
      (node (ref "C12") (pin "2") (pinfunction "2_2") (pintype "passive"))
      (node (ref "U3") (pin "2") (pinfunction "GND_2") (pintype "power_in"))
      (node (ref "VS") (pin "37") (pinfunction "AGND0_37") (pintype "power_in"))
      (node (ref "VS") (pin "40") (pinfunction "AGND1_40") (pintype "power_in"))
      (node (ref "VS") (pin "41") (pinfunction "AGND2_41") (pintype "power_in"))
      (node (ref "VS") (pin "47") (pinfunction "AGND3_47") (pintype "power_in"))
      (node (ref "VS_C13") (pin "2") (pinfunction "2_2") (pintype "passive"))
      (node (ref "VS_C14") (pin "2") (pinfunction "2_2") (pintype "passive"))
      (node (ref "VS_C3") (pin "1") (pinfunction "1_1") (pintype "passive"))
      (node (ref "VS_C4") (pin "1") (pinfunction "1_1") (pintype "passive"))
      (node (ref "VS_C5") (pin "1") (pinfunction "1_1") (pintype "passive"))
      (node (ref "VS_C6") (pin "1") (pinfunction "1_1") (pintype "passive"))
      (node (ref "VS_CL2") (pin "2") (pinfunction "2_2") (pintype "passive"))
      (node (ref "VS_CR2") (pin "2") (pinfunction "2_2") (pintype "passive"))
      (node (ref "VS_GND") (pin "2") (pinfunction "2_2") (pintype "passive"))
      (node (ref "VS_R6") (pin "2") (pinfunction "2_2") (pintype "passive"))
      (node (ref "VS_R7") (pin "2") (pinfunction "2_2") (pintype "passive"))
      (node (ref "~NUDEV~1") (pin "GNDA") (pinfunction "GNDA_GNDA") (pintype "power_in"))
    )
    (net (code "30") (name "FM_CS") (class "Default")
      (node (ref "ARM") (pin "73") (pinfunction "SSI1FSS/PE1_73") (pintype "bidirectional"))
      (node (ref "FM") (pin "1") (pinfunction "-CS_1") (pintype "input"))
      (node (ref "FM_R1") (pin "1") (pinfunction "1_1") (pintype "passive"))
    )
    (net (code "31") (name "GND") (class "Default")
      (node (ref "ARM") (pin "15") (pinfunction "GND1_15") (pintype "power_in"))
      (node (ref "ARM") (pin "21") (pinfunction "GND2_21") (pintype "power_in"))
      (node (ref "ARM") (pin "33") (pinfunction "GND3_33") (pintype "power_in"))
      (node (ref "ARM") (pin "39") (pinfunction "GND4_39") (pintype "power_in"))
      (node (ref "ARM") (pin "4") (pinfunction "GNDA0_4") (pintype "power_in"))
      (node (ref "ARM") (pin "41") (pinfunction "GNDPHY0_41") (pintype "power_in"))
      (node (ref "ARM") (pin "42") (pinfunction "GNDPHY1_42") (pintype "power_in"))
      (node (ref "ARM") (pin "45") (pinfunction "GND5_45") (pintype "power_in"))
      (node (ref "ARM") (pin "50") (pinfunction "~{WAKE}_50") (pintype "input"))
      (node (ref "ARM") (pin "54") (pinfunction "GND6_54") (pintype "power_in"))
      (node (ref "ARM") (pin "57") (pinfunction "GND7_57") (pintype "power_in"))
      (node (ref "ARM") (pin "63") (pinfunction "GND8_63") (pintype "power_in"))
      (node (ref "ARM") (pin "65") (pinfunction "CMOD0_65") (pintype "bidirectional"))
      (node (ref "ARM") (pin "69") (pinfunction "GND9_69") (pintype "power_in"))
      (node (ref "ARM") (pin "76") (pinfunction "CMOD1_76") (pintype "bidirectional"))
      (node (ref "ARM") (pin "82") (pinfunction "GND10_82") (pintype "power_in"))
      (node (ref "ARM") (pin "85") (pinfunction "GNDPHY2_85") (pintype "power_in"))
      (node (ref "ARM") (pin "86") (pinfunction "GNDPHY3_86") (pintype "power_in"))
      (node (ref "ARM") (pin "87") (pinfunction "GND11_87") (pintype "power_in"))
      (node (ref "ARM") (pin "9") (pinfunction "GND0_9") (pintype "power_in"))
      (node (ref "ARM") (pin "94") (pinfunction "GND12_94") (pintype "power_in"))
      (node (ref "ARM") (pin "97") (pinfunction "GNDA1_97") (pintype "power_in"))
      (node (ref "ARM_C1") (pin "2") (pinfunction "2_2") (pintype "passive"))
      (node (ref "ARM_C10") (pin "2") (pinfunction "2_2") (pintype "passive"))
      (node (ref "ARM_C11") (pin "2") (pinfunction "2_2") (pintype "passive"))
      (node (ref "ARM_C12") (pin "2") (pinfunction "2_2") (pintype "passive"))
      (node (ref "ARM_C2") (pin "2") (pinfunction "2_2") (pintype "passive"))
      (node (ref "ARM_C3") (pin "2") (pinfunction "2_2") (pintype "passive"))
      (node (ref "ARM_C4") (pin "2") (pinfunction "2_2") (pintype "passive"))
      (node (ref "ARM_C5") (pin "2") (pinfunction "2_2") (pintype "passive"))
      (node (ref "ARM_C6") (pin "2") (pinfunction "2_2") (pintype "passive"))
      (node (ref "ARM_C7") (pin "2") (pinfunction "2_2") (pintype "passive"))
      (node (ref "ARM_C8") (pin "2") (pinfunction "2_2") (pintype "passive"))
      (node (ref "ARM_C9") (pin "2") (pinfunction "2_2") (pintype "passive"))
      (node (ref "C1") (pin "-") (pinfunction "-_-") (pintype "passive"))
      (node (ref "C13") (pin "1") (pinfunction "1_1") (pintype "passive"))
      (node (ref "C14") (pin "2") (pinfunction "2_2") (pintype "passive"))
      (node (ref "C15") (pin "2") (pinfunction "2_2") (pintype "passive"))
      (node (ref "C2") (pin "2") (pinfunction "2_2") (pintype "passive"))
      (node (ref "C4") (pin "-") (pinfunction "-_-") (pintype "passive"))
      (node (ref "C5") (pin "2") (pinfunction "2_2") (pintype "passive"))
      (node (ref "C6") (pin "1") (pinfunction "1_1") (pintype "passive"))
      (node (ref "C7") (pin "2") (pinfunction "2_2") (pintype "passive"))
      (node (ref "C8") (pin "2") (pinfunction "2_2") (pintype "passive"))
      (node (ref "C9") (pin "2") (pinfunction "2_2") (pintype "passive"))
      (node (ref "D1") (pin "A") (pinfunction "A_A") (pintype "passive"))
      (node (ref "EXP") (pin "1") (pinfunction "1_1") (pintype "passive"))
      (node (ref "EXP") (pin "2") (pinfunction "2_2") (pintype "passive"))
      (node (ref "EXP_C1") (pin "1") (pinfunction "1_1") (pintype "passive"))
      (node (ref "EXP_C2") (pin "1") (pinfunction "1_1") (pintype "passive"))
      (node (ref "FM") (pin "4") (pinfunction "GND_4") (pintype "power_in"))
      (node (ref "FM_C1") (pin "2") (pinfunction "2_2") (pintype "passive"))
      (node (ref "GND") (pin "1") (pinfunction "P_1") (pintype "passive"))
      (node (ref "JTAG") (pin "10") (pinfunction "10_10") (pintype "passive"))
      (node (ref "JTAG") (pin "12") (pinfunction "12_12") (pintype "passive"))
      (node (ref "JTAG") (pin "14") (pinfunction "14_14") (pintype "passive"))
      (node (ref "JTAG") (pin "16") (pinfunction "16_16") (pintype "passive"))
      (node (ref "JTAG") (pin "18") (pinfunction "18_18") (pintype "passive"))
      (node (ref "JTAG") (pin "20") (pinfunction "20_20") (pintype "passive"))
      (node (ref "JTAG") (pin "4") (pinfunction "4_4") (pintype "passive"))
      (node (ref "JTAG") (pin "6") (pinfunction "6_6") (pintype "passive"))
      (node (ref "JTAG") (pin "8") (pinfunction "8_8") (pintype "passive"))
      (node (ref "POE") (pin "5") (pinfunction "RTN_5") (pintype "output"))
      (node (ref "RJ_C1") (pin "2") (pinfunction "2_2") (pintype "passive"))
      (node (ref "RJ_C2") (pin "1") (pinfunction "1_1") (pintype "passive"))
      (node (ref "RJ_C3") (pin "1") (pinfunction "1_1") (pintype "passive"))
      (node (ref "RJ_C4") (pin "1") (pinfunction "1_1") (pintype "passive"))
      (node (ref "RJ_C5") (pin "1") (pinfunction "1_1") (pintype "passive"))
      (node (ref "RJ_C6") (pin "1") (pinfunction "1_1") (pintype "passive"))
      (node (ref "RJ_C7") (pin "1") (pinfunction "1_1") (pintype "passive"))
      (node (ref "SD") (pin "6") (pinfunction "6_6") (pintype "bidirectional"))
      (node (ref "SD_C1") (pin "2") (pinfunction "2_2") (pintype "passive"))
      (node (ref "SD_C2") (pin "1") (pinfunction "1_1") (pintype "passive"))
      (node (ref "SD_C3") (pin "1") (pinfunction "1_1") (pintype "passive"))
      (node (ref "U1") (pin "3") (pinfunction "SGND_3") (pintype "power_in"))
      (node (ref "U1") (pin "6") (pinfunction "GND_6") (pintype "power_in"))
      (node (ref "U2") (pin "2") (pinfunction "GND_2") (pintype "power_in"))
      (node (ref "U4") (pin "2") (pinfunction "GND_2") (pintype "power_in"))
      (node (ref "USB") (pin "GND") (pinfunction "GND_GND") (pintype "bidirectional"))
      (node (ref "USB_C1") (pin "1") (pinfunction "1_1") (pintype "passive"))
      (node (ref "USB_C2") (pin "2") (pinfunction "2_2") (pintype "passive"))
      (node (ref "USB_C3") (pin "2") (pinfunction "2_2") (pintype "passive"))
      (node (ref "USB_C4") (pin "1") (pinfunction "1_1") (pintype "passive"))
      (node (ref "VS") (pin "16") (pinfunction "GND1_16") (pintype "power_in"))
      (node (ref "VS") (pin "20") (pinfunction "GND2_20") (pintype "power_in"))
      (node (ref "VS") (pin "21") (pinfunction "GND3_21") (pintype "power_in"))
      (node (ref "VS") (pin "22") (pinfunction "GND4_22") (pintype "power_in"))
      (node (ref "VS") (pin "35") (pinfunction "GND5_35") (pintype "power_in"))
      (node (ref "VS") (pin "4") (pinfunction "GND0_4") (pintype "power_in"))
      (node (ref "VS_C1") (pin "2") (pinfunction "2_2") (pintype "passive"))
      (node (ref "VS_C10") (pin "2") (pinfunction "2_2") (pintype "passive"))
      (node (ref "VS_C11") (pin "2") (pinfunction "2_2") (pintype "passive"))
      (node (ref "VS_C12") (pin "2") (pinfunction "2_2") (pintype "passive"))
      (node (ref "VS_C2") (pin "2") (pinfunction "2_2") (pintype "passive"))
      (node (ref "VS_C7") (pin "2") (pinfunction "2_2") (pintype "passive"))
      (node (ref "VS_C8") (pin "2") (pinfunction "2_2") (pintype "passive"))
      (node (ref "VS_C9") (pin "2") (pinfunction "2_2") (pintype "passive"))
      (node (ref "VS_R2") (pin "1") (pinfunction "1_1") (pintype "passive"))
      (node (ref "~NUDEV~1") (pin "GND") (pinfunction "GND_GND") (pintype "power_in"))
    )
    (net (code "32") (name "LED1") (class "Default")
      (node (ref "ARM") (pin "59") (pinfunction "LED0/PF3_59") (pintype "bidirectional"))
      (node (ref "RJ_R5") (pin "2") (pinfunction "2_2") (pintype "passive"))
    )
    (net (code "33") (name "LED2") (class "Default")
      (node (ref "ARM") (pin "60") (pinfunction "LED1/PF2_60") (pintype "bidirectional"))
      (node (ref "RJ_R6") (pin "2") (pinfunction "2_2") (pintype "passive"))
    )
    (net (code "34") (name "Net-(ARM-MDIO)") (class "Default")
      (node (ref "ARM") (pin "58") (pinfunction "MDIO_58") (pintype "bidirectional"))
      (node (ref "ARM_R3") (pin "1") (pinfunction "1_1") (pintype "passive"))
    )
    (net (code "35") (name "Net-(ARM-OSC0)") (class "Default")
      (node (ref "ARM") (pin "48") (pinfunction "OSC0_48") (pintype "bidirectional"))
      (node (ref "ARM_C1") (pin "1") (pinfunction "1_1") (pintype "passive"))
      (node (ref "ARM_Q1") (pin "2") (pinfunction "2_2") (pintype "passive"))
    )
    (net (code "36") (name "Net-(ARM-OSC1)") (class "Default")
      (node (ref "ARM") (pin "49") (pinfunction "OSC1_49") (pintype "bidirectional"))
      (node (ref "ARM_C2") (pin "1") (pinfunction "1_1") (pintype "passive"))
      (node (ref "ARM_Q1") (pin "1") (pinfunction "1_1") (pintype "passive"))
    )
    (net (code "37") (name "Net-(ARM-XTALNPHY)") (class "Default")
      (node (ref "ARM") (pin "17") (pinfunction "XTALNPHY_17") (pintype "bidirectional"))
      (node (ref "ARM_C4") (pin "1") (pinfunction "1_1") (pintype "passive"))
      (node (ref "ARM_Q2") (pin "2") (pinfunction "2_2") (pintype "passive"))
    )
    (net (code "38") (name "Net-(ARM-XTALPPHY)") (class "Default")
      (node (ref "ARM") (pin "16") (pinfunction "XTALPPHY_16") (pintype "bidirectional"))
      (node (ref "ARM_C3") (pin "1") (pinfunction "1_1") (pintype "passive"))
      (node (ref "ARM_Q2") (pin "1") (pinfunction "1_1") (pintype "passive"))
    )
    (net (code "39") (name "Net-(ARM-~{RESET})") (class "Default")
      (node (ref "ARM") (pin "64") (pinfunction "~{RESET}_64") (pintype "input"))
      (node (ref "ARM_R1") (pin "2") (pinfunction "2_2") (pintype "passive"))
    )
    (net (code "40") (name "Net-(OUT-Pad1)") (class "Default")
      (node (ref "OUT") (pin "1") (pinfunction "1_1") (pintype "passive"))
      (node (ref "VS_GBUF") (pin "2") (pinfunction "2_2") (pintype "passive"))
      (node (ref "VS_GND") (pin "1") (pinfunction "1_1") (pintype "passive"))
    )
    (net (code "41") (name "Net-(OUT-Pad2)") (class "Default")
      (node (ref "OUT") (pin "2") (pinfunction "2_2") (pintype "passive"))
      (node (ref "VS_CL") (pin "2") (pinfunction "2_2") (pintype "passive"))
      (node (ref "VS_R7") (pin "1") (pinfunction "1_1") (pintype "passive"))
    )
    (net (code "42") (name "Net-(OUT-Pad3)") (class "Default")
      (node (ref "OUT") (pin "3") (pinfunction "3_3") (pintype "passive"))
      (node (ref "VS_CR") (pin "2") (pinfunction "2_2") (pintype "passive"))
      (node (ref "VS_R6") (pin "1") (pinfunction "1_1") (pintype "passive"))
    )
    (net (code "43") (name "Net-(POE-CLASS)") (class "Default")
      (node (ref "POE") (pin "2") (pinfunction "CLASS_2") (pintype "output"))
      (node (ref "POE_CLA") (pin "2") (pinfunction "2_2") (pintype "passive"))
    )
    (net (code "44") (name "Net-(POE-DET)") (class "Default")
      (node (ref "POE") (pin "3") (pinfunction "DET_3") (pintype "output"))
      (node (ref "POE_DET") (pin "2") (pinfunction "2_2") (pintype "passive"))
    )
    (net (code "45") (name "Net-(POE-ILM)") (class "Default")
      (node (ref "POE") (pin "1") (pinfunction "ILM_1") (pintype "output"))
      (node (ref "POE_ILM") (pin "2") (pinfunction "2_2") (pintype "passive"))
    )
    (net (code "46") (name "Net-(POE-POE-)") (class "Default")
      (node (ref "POE") (pin "4") (pinfunction "POE-_4") (pintype "power_in"))
      (node (ref "POE_CLA") (pin "1") (pinfunction "1_1") (pintype "passive"))
      (node (ref "POE_D1") (pin "A") (pinfunction "A_A") (pintype "passive"))
      (node (ref "POE_ILM") (pin "1") (pinfunction "1_1") (pintype "passive"))
      (node (ref "RJ") (pin "10") (pinfunction "POE-_10") (pintype "power_in"))
    )
    (net (code "47") (name "Net-(PWR+-P)") (class "Default")
      (node (ref "FUSE") (pin "1") (pinfunction "1_1") (pintype "passive"))
      (node (ref "PWR+") (pin "1") (pinfunction "P_1") (pintype "passive"))
    )
    (net (code "48") (name "Net-(RJ-PadLED1-)") (class "Default")
      (node (ref "RJ") (pin "LED1-") (pinfunction "LED1-_LED1-") (pintype "input"))
      (node (ref "RJ_R5") (pin "1") (pinfunction "1_1") (pintype "passive"))
    )
    (net (code "49") (name "Net-(RJ-PadLED2-)") (class "Default")
      (node (ref "RJ") (pin "LED2-") (pinfunction "LED2-_LED2-") (pintype "input"))
      (node (ref "RJ_R6") (pin "1") (pinfunction "1_1") (pintype "passive"))
    )
    (net (code "50") (name "Net-(RJ_C3-Pad2)") (class "Default")
      (node (ref "RJ_C3") (pin "2") (pinfunction "2_2") (pintype "passive"))
      (node (ref "RJ_R1") (pin "2") (pinfunction "2_2") (pintype "passive"))
      (node (ref "RJ_R2") (pin "2") (pinfunction "2_2") (pintype "passive"))
    )
    (net (code "51") (name "Net-(RJ_C6-Pad2)") (class "Default")
      (node (ref "RJ_C6") (pin "2") (pinfunction "2_2") (pintype "passive"))
      (node (ref "RJ_R3") (pin "2") (pinfunction "2_2") (pintype "passive"))
      (node (ref "RJ_R4") (pin "2") (pinfunction "2_2") (pintype "passive"))
    )
    (net (code "52") (name "Net-(SD-Pad1)") (class "Default")
      (node (ref "SD") (pin "1") (pinfunction "1_1") (pintype "bidirectional"))
      (node (ref "SD_R5") (pin "2") (pinfunction "2_2") (pintype "passive"))
    )
    (net (code "53") (name "Net-(SD-Pad8)") (class "Default")
      (node (ref "SD") (pin "8") (pinfunction "8_8") (pintype "bidirectional"))
      (node (ref "SD_R2") (pin "2") (pinfunction "2_2") (pintype "passive"))
    )
    (net (code "54") (name "Net-(SD_Q1-D)") (class "Default")
      (node (ref "SD") (pin "4") (pinfunction "4_4") (pintype "bidirectional"))
      (node (ref "SD_C1") (pin "1") (pinfunction "1_1") (pintype "passive"))
      (node (ref "SD_Q1") (pin "3") (pinfunction "D_3") (pintype "passive"))
      (node (ref "SD_R2") (pin "1") (pinfunction "1_1") (pintype "passive"))
      (node (ref "SD_R3") (pin "1") (pinfunction "1_1") (pintype "passive"))
      (node (ref "SD_R4") (pin "1") (pinfunction "1_1") (pintype "passive"))
      (node (ref "SD_R5") (pin "1") (pinfunction "1_1") (pintype "passive"))
    )
    (net (code "55") (name "Net-(U1-BST)") (class "Default")
      (node (ref "C3") (pin "1") (pinfunction "1_1") (pintype "passive"))
      (node (ref "U1") (pin "1") (pinfunction "BST_1") (pintype "power_in"))
    )
    (net (code "56") (name "Net-(U1-OUT)") (class "Default")
      (node (ref "C3") (pin "2") (pinfunction "2_2") (pintype "passive"))
      (node (ref "D1") (pin "C") (pinfunction "C_C") (pintype "passive"))
      (node (ref "L1") (pin "1") (pinfunction "1_1") (pintype "passive"))
      (node (ref "U1") (pin "8") (pinfunction "OUT_8") (pintype "power_in"))
    )
    (net (code "57") (name "Net-(U1-VD)") (class "Default")
      (node (ref "C2") (pin "1") (pinfunction "1_1") (pintype "passive"))
      (node (ref "U1") (pin "2") (pinfunction "VD_2") (pintype "input"))
    )
    (net (code "58") (name "Net-(U2-BYPASS)") (class "Default")
      (node (ref "C7") (pin "1") (pinfunction "1_1") (pintype "passive"))
      (node (ref "U2") (pin "4") (pinfunction "BYPASS_4") (pintype "input"))
    )
    (net (code "59") (name "Net-(U3-BYPASS)") (class "Default")
      (node (ref "C11") (pin "1") (pinfunction "1_1") (pintype "passive"))
      (node (ref "U3") (pin "4") (pinfunction "BYPASS_4") (pintype "input"))
    )
    (net (code "60") (name "Net-(U3-ON-~{OFF})") (class "Default")
      (node (ref "C10") (pin "2") (pinfunction "2_2") (pintype "passive"))
      (node (ref "L2") (pin "2") (pinfunction "2_2") (pintype "passive"))
      (node (ref "U3") (pin "1") (pinfunction "VIN_1") (pintype "power_in"))
      (node (ref "U3") (pin "3") (pinfunction "ON-~{OFF}_3") (pintype "input"))
    )
    (net (code "61") (name "Net-(U4-BYPASS)") (class "Default")
      (node (ref "C14") (pin "1") (pinfunction "1_1") (pintype "passive"))
      (node (ref "U4") (pin "4") (pinfunction "BYPASS_4") (pintype "input"))
    )
    (net (code "62") (name "Net-(USB_Q1-D)") (class "Default")
      (node (ref "USB") (pin "VBUS") (pinfunction "VBUS_VBUS") (pintype "bidirectional"))
      (node (ref "USB_C2") (pin "1") (pinfunction "1_1") (pintype "passive"))
      (node (ref "USB_C3") (pin "1") (pinfunction "1_1") (pintype "passive"))
      (node (ref "USB_Q1") (pin "3") (pinfunction "D_3") (pintype "passive"))
    )
    (net (code "63") (name "Net-(USB_Q1-G)") (class "Default")
      (node (ref "USB_C1") (pin "2") (pinfunction "2_2") (pintype "passive"))
      (node (ref "USB_Q1") (pin "1") (pinfunction "G_1") (pintype "passive"))
      (node (ref "USB_R1") (pin "2") (pinfunction "2_2") (pintype "passive"))
      (node (ref "USB_R2") (pin "1") (pinfunction "1_1") (pintype "passive"))
    )
    (net (code "64") (name "Net-(USB_Q1-S)") (class "Default")
      (node (ref "USB_C4") (pin "2") (pinfunction "2_2") (pintype "passive"))
      (node (ref "USB_L1") (pin "2") (pinfunction "2_2") (pintype "passive"))
      (node (ref "USB_Q1") (pin "2") (pinfunction "S_2") (pintype "passive"))
      (node (ref "USB_R1") (pin "1") (pinfunction "1_1") (pintype "passive"))
    )
    (net (code "65") (name "Net-(VS-GBUF)") (class "Default")
      (node (ref "VS") (pin "42") (pinfunction "GBUF_42") (pintype "passive"))
      (node (ref "VS_GBUF") (pin "1") (pinfunction "1_1") (pintype "passive"))
      (node (ref "VS_R5") (pin "2") (pinfunction "2_2") (pintype "passive"))
    )
    (net (code "66") (name "Net-(VS-GPIO0)") (class "Default")
      (node (ref "VS") (pin "10") (pinfunction "GPIO3_10") (pintype "bidirectional"))
      (node (ref "VS") (pin "11") (pinfunction "GPIO6_11") (pintype "bidirectional"))
      (node (ref "VS") (pin "12") (pinfunction "GPIO7_12") (pintype "bidirectional"))
      (node (ref "VS") (pin "25") (pinfunction "GPIO5_25") (pintype "bidirectional"))
      (node (ref "VS") (pin "33") (pinfunction "GPIO0_33") (pintype "bidirectional"))
      (node (ref "VS") (pin "34") (pinfunction "GPIO1_34") (pintype "bidirectional"))
      (node (ref "VS") (pin "36") (pinfunction "GPIO4_36") (pintype "bidirectional"))
      (node (ref "VS") (pin "9") (pinfunction "GPIO2_9") (pintype "bidirectional"))
      (node (ref "VS_R2") (pin "2") (pinfunction "2_2") (pintype "passive"))
    )
    (net (code "67") (name "Net-(VS-LEFT)") (class "Default")
      (node (ref "VS") (pin "46") (pinfunction "LEFT_46") (pintype "passive"))
      (node (ref "VS_R3") (pin "2") (pinfunction "2_2") (pintype "passive"))
      (node (ref "VS_RL") (pin "1") (pinfunction "1_1") (pintype "passive"))
    )
    (net (code "68") (name "Net-(VS-RCAP)") (class "Default")
      (node (ref "VS") (pin "44") (pinfunction "RCAP_44") (pintype "passive"))
      (node (ref "VS_C6") (pin "2") (pinfunction "2_2") (pintype "passive"))
    )
    (net (code "69") (name "Net-(VS-RIGHT)") (class "Default")
      (node (ref "VS") (pin "39") (pinfunction "RIGHT_39") (pintype "passive"))
      (node (ref "VS_R4") (pin "2") (pinfunction "2_2") (pintype "passive"))
      (node (ref "VS_RR") (pin "1") (pinfunction "1_1") (pintype "passive"))
    )
    (net (code "70") (name "Net-(VS-XTALI)") (class "Default")
      (node (ref "VS") (pin "18") (pinfunction "XTALI_18") (pintype "passive"))
      (node (ref "VS_C2") (pin "1") (pinfunction "1_1") (pintype "passive"))
      (node (ref "VS_Q1") (pin "1") (pinfunction "1_1") (pintype "passive"))
      (node (ref "VS_R1") (pin "2") (pinfunction "2_2") (pintype "passive"))
    )
    (net (code "71") (name "Net-(VS-XTALO)") (class "Default")
      (node (ref "VS") (pin "17") (pinfunction "XTALO_17") (pintype "passive"))
      (node (ref "VS_C1") (pin "1") (pinfunction "1_1") (pintype "passive"))
      (node (ref "VS_Q1") (pin "2") (pinfunction "2_2") (pintype "passive"))
      (node (ref "VS_R1") (pin "1") (pinfunction "1_1") (pintype "passive"))
    )
    (net (code "72") (name "Net-(VS_C3-Pad2)") (class "Default")
      (node (ref "VS_C3") (pin "2") (pinfunction "2_2") (pintype "passive"))
      (node (ref "VS_R3") (pin "1") (pinfunction "1_1") (pintype "passive"))
    )
    (net (code "73") (name "Net-(VS_C4-Pad2)") (class "Default")
      (node (ref "VS_C4") (pin "2") (pinfunction "2_2") (pintype "passive"))
      (node (ref "VS_R4") (pin "1") (pinfunction "1_1") (pintype "passive"))
    )
    (net (code "74") (name "Net-(VS_C5-Pad2)") (class "Default")
      (node (ref "VS_C5") (pin "2") (pinfunction "2_2") (pintype "passive"))
      (node (ref "VS_R5") (pin "1") (pinfunction "1_1") (pintype "passive"))
    )
    (net (code "75") (name "Net-(VS_CL-Pad1)") (class "Default")
      (node (ref "VS_CL") (pin "1") (pinfunction "1_1") (pintype "passive"))
      (node (ref "VS_CL2") (pin "1") (pinfunction "1_1") (pintype "passive"))
      (node (ref "VS_RL") (pin "2") (pinfunction "2_2") (pintype "passive"))
    )
    (net (code "76") (name "Net-(VS_CR-Pad1)") (class "Default")
      (node (ref "VS_CR") (pin "1") (pinfunction "1_1") (pintype "passive"))
      (node (ref "VS_CR2") (pin "1") (pinfunction "1_1") (pintype "passive"))
      (node (ref "VS_RR") (pin "2") (pinfunction "2_2") (pintype "passive"))
    )
    (net (code "77") (name "POE+") (class "Default")
      (node (ref "POE+") (pin "1") (pinfunction "P_1") (pintype "passive"))
      (node (ref "RJ") (pin "9") (pinfunction "POE+_9") (pintype "power_in"))
    )
    (net (code "78") (name "PWR+") (class "Default")
      (node (ref "C1") (pin "+") (pinfunction "+_+") (pintype "passive"))
      (node (ref "FUSE") (pin "2") (pinfunction "2_2") (pintype "passive"))
      (node (ref "POE") (pin "8") (pinfunction "POE+_8") (pintype "power_in"))
      (node (ref "POE_D1") (pin "C") (pinfunction "C_C") (pintype "passive"))
      (node (ref "POE_DET") (pin "1") (pinfunction "1_1") (pintype "passive"))
      (node (ref "U1") (pin "5") (pinfunction "ON/~{OFF}_5") (pintype "input"))
      (node (ref "U1") (pin "7") (pinfunction "VIN_7") (pintype "power_in"))
    )
    (net (code "79") (name "RD+") (class "Default")
      (node (ref "ARM") (pin "40") (pinfunction "RXIP_40") (pintype "bidirectional"))
      (node (ref "RJ") (pin "1") (pinfunction "RD+_1") (pintype "bidirectional"))
      (node (ref "RJ_C2") (pin "2") (pinfunction "2_2") (pintype "passive"))
      (node (ref "RJ_R1") (pin "1") (pinfunction "1_1") (pintype "passive"))
    )
    (net (code "80") (name "RD-") (class "Default")
      (node (ref "ARM") (pin "37") (pinfunction "RXIN_37") (pintype "bidirectional"))
      (node (ref "RJ") (pin "2") (pinfunction "RD-_2") (pintype "bidirectional"))
      (node (ref "RJ_C4") (pin "2") (pinfunction "2_2") (pintype "passive"))
      (node (ref "RJ_R2") (pin "1") (pinfunction "1_1") (pintype "passive"))
    )
    (net (code "81") (name "SCK") (class "Default")
      (node (ref "ARM") (pin "72") (pinfunction "SSI1CLK/PE0_72") (pintype "bidirectional"))
      (node (ref "EXP") (pin "11") (pinfunction "11_11") (pintype "passive"))
      (node (ref "FM") (pin "6") (pinfunction "CLK_6") (pintype "input"))
      (node (ref "SD") (pin "5") (pinfunction "5_5") (pintype "bidirectional"))
    )
    (net (code "82") (name "SD_CS") (class "Default")
      (node (ref "ARM") (pin "67") (pinfunction "PWM3/PB1_67") (pintype "bidirectional"))
      (node (ref "SD") (pin "2") (pinfunction "2_2") (pintype "bidirectional"))
      (node (ref "SD_R4") (pin "2") (pinfunction "2_2") (pintype "passive"))
    )
    (net (code "83") (name "SD_PWR") (class "Default")
      (node (ref "ARM") (pin "66") (pinfunction "PWM2/PB0_66") (pintype "bidirectional"))
      (node (ref "SD_Q1") (pin "1") (pinfunction "G_1") (pintype "passive"))
      (node (ref "SD_R1") (pin "2") (pinfunction "2_2") (pintype "passive"))
    )
    (net (code "84") (name "SI") (class "Default")
      (node (ref "ARM") (pin "75") (pinfunction "SSI1TX/PE3_75") (pintype "bidirectional"))
      (node (ref "EXP") (pin "13") (pinfunction "13_13") (pintype "passive"))
      (node (ref "FM") (pin "5") (pinfunction "DI_5") (pintype "input"))
      (node (ref "SD") (pin "3") (pinfunction "3_3") (pintype "bidirectional"))
    )
    (net (code "85") (name "SO") (class "Default")
      (node (ref "ARM") (pin "74") (pinfunction "SSI1RX/PE2_74") (pintype "bidirectional"))
      (node (ref "EXP") (pin "12") (pinfunction "12_12") (pintype "passive"))
      (node (ref "FM") (pin "2") (pinfunction "DO_2") (pintype "output"))
      (node (ref "SD") (pin "7") (pinfunction "7_7") (pintype "bidirectional"))
      (node (ref "SD_R3") (pin "2") (pinfunction "2_2") (pintype "passive"))
    )
    (net (code "86") (name "TCK") (class "Default")
      (node (ref "ARM") (pin "80") (pinfunction "TCK/SWCLK/PC0_80") (pintype "bidirectional"))
      (node (ref "JTAG") (pin "9") (pinfunction "9_9") (pintype "passive"))
    )
    (net (code "87") (name "TD+") (class "Default")
      (node (ref "ARM") (pin "43") (pinfunction "TXOP_43") (pintype "bidirectional"))
      (node (ref "RJ") (pin "5") (pinfunction "TD+_5") (pintype "bidirectional"))
      (node (ref "RJ_C5") (pin "2") (pinfunction "2_2") (pintype "passive"))
      (node (ref "RJ_R3") (pin "1") (pinfunction "1_1") (pintype "passive"))
    )
    (net (code "88") (name "TD-") (class "Default")
      (node (ref "ARM") (pin "46") (pinfunction "TXON_46") (pintype "bidirectional"))
      (node (ref "RJ") (pin "6") (pinfunction "TD-_6") (pintype "bidirectional"))
      (node (ref "RJ_C7") (pin "2") (pinfunction "2_2") (pintype "passive"))
      (node (ref "RJ_R4") (pin "1") (pinfunction "1_1") (pintype "passive"))
    )
    (net (code "89") (name "TDI") (class "Default")
      (node (ref "ARM") (pin "78") (pinfunction "TDI/PC2_78") (pintype "bidirectional"))
      (node (ref "JTAG") (pin "5") (pinfunction "5_5") (pintype "passive"))
    )
    (net (code "90") (name "TDO") (class "Default")
      (node (ref "ARM") (pin "77") (pinfunction "TDO/SWO/PC3_77") (pintype "bidirectional"))
      (node (ref "JTAG") (pin "13") (pinfunction "13_13") (pintype "passive"))
    )
    (net (code "91") (name "TMS") (class "Default")
      (node (ref "ARM") (pin "79") (pinfunction "TMS/SWDIO/PC1_79") (pintype "bidirectional"))
      (node (ref "JTAG") (pin "7") (pinfunction "7_7") (pintype "passive"))
    )
    (net (code "92") (name "TRST") (class "Default")
      (node (ref "ARM") (pin "89") (pinfunction "TRST/PB7_89") (pintype "bidirectional"))
      (node (ref "ARM_R2") (pin "1") (pinfunction "1_1") (pintype "passive"))
      (node (ref "JTAG") (pin "3") (pinfunction "3_3") (pintype "passive"))
    )
    (net (code "93") (name "USB_PWR") (class "Default")
      (node (ref "ARM") (pin "61") (pinfunction "PWM1/PF1_61") (pintype "bidirectional"))
      (node (ref "USB_R2") (pin "2") (pinfunction "2_2") (pintype "passive"))
    )
    (net (code "94") (name "VBAT") (class "Default")
      (node (ref "ARM") (pin "55") (pinfunction "VBAT_55") (pintype "power_in"))
    )
    (net (code "95") (name "VCCIO") (class "Default")
      (node (ref "ARM") (pin "14") (pinfunction "VCC25_0_14") (pintype "power_in"))
      (node (ref "ARM") (pin "38") (pinfunction "VCC25_1_38") (pintype "power_in"))
      (node (ref "ARM") (pin "62") (pinfunction "VCC25_2_62") (pintype "power_in"))
      (node (ref "ARM") (pin "7") (pinfunction "LDO_7") (pintype "power_in"))
      (node (ref "ARM") (pin "88") (pinfunction "VCC25_3_88") (pintype "power_in"))
      (node (ref "ARM_C10") (pin "1") (pinfunction "1_1") (pintype "passive"))
      (node (ref "ARM_C11") (pin "1") (pinfunction "1_1") (pintype "passive"))
      (node (ref "ARM_C12") (pin "1") (pinfunction "1_1") (pintype "passive"))
      (node (ref "ARM_C9") (pin "1") (pinfunction "1_1") (pintype "passive"))
    )
    (net (code "96") (name "VS_CS") (class "Default")
      (node (ref "ARM") (pin "34") (pinfunction "CCP1/PA6_34") (pintype "bidirectional"))
      (node (ref "VS") (pin "23") (pinfunction "~{CS}_23") (pintype "input"))
    )
    (net (code "97") (name "VS_DCS") (class "Default")
      (node (ref "ARM") (pin "29") (pinfunction "SSI0FSS/PA3_29") (pintype "bidirectional"))
      (node (ref "VS") (pin "13") (pinfunction "~{DCS}_13") (pintype "input"))
    )
    (net (code "98") (name "VS_DREQ") (class "Default")
      (node (ref "ARM") (pin "27") (pinfunction "U0TX/PA1_27") (pintype "bidirectional"))
      (node (ref "VS") (pin "8") (pinfunction "~{DREQ}_8") (pintype "input"))
    )
    (net (code "99") (name "VS_RST") (class "Default")
      (node (ref "ARM") (pin "35") (pinfunction "CCP4/PA7_35") (pintype "bidirectional"))
      (node (ref "VS") (pin "3") (pinfunction "~{RESET}_3") (pintype "input"))
    )
    (net (code "100") (name "VS_SCK") (class "Default")
      (node (ref "ARM") (pin "28") (pinfunction "SSI0CLK/PA2_28") (pintype "bidirectional"))
      (node (ref "VS") (pin "28") (pinfunction "SCLK_28") (pintype "input"))
    )
    (net (code "101") (name "VS_SI") (class "Default")
      (node (ref "ARM") (pin "31") (pinfunction "SSI0TX/PA5_31") (pintype "bidirectional"))
      (node (ref "VS") (pin "29") (pinfunction "SI_29") (pintype "input"))
    )
    (net (code "102") (name "VS_SO") (class "Default")
      (node (ref "ARM") (pin "30") (pinfunction "SSI0RX/PA4_30") (pintype "bidirectional"))
      (node (ref "VS") (pin "30") (pinfunction "SO_30") (pintype "output"))
    )
    (net (code "103") (name "unconnected-(ARM-U0RX{slash}PA0-Pad26)") (class "Default")
      (node (ref "ARM") (pin "26") (pinfunction "U0RX/PA0_26") (pintype "bidirectional"))
    )
    (net (code "104") (name "unconnected-(ARM-XOSC0-Pad52)") (class "Default")
      (node (ref "ARM") (pin "52") (pinfunction "XOSC0_52") (pintype "bidirectional"))
    )
    (net (code "105") (name "unconnected-(ARM-XOSC1-Pad53)") (class "Default")
      (node (ref "ARM") (pin "53") (pinfunction "XOSC1_53") (pintype "bidirectional"))
    )
    (net (code "106") (name "unconnected-(ARM-~{HIB}-Pad51)") (class "Default")
      (node (ref "ARM") (pin "51") (pinfunction "~{HIB}_51") (pintype "output"))
    )
    (net (code "107") (name "unconnected-(EXP-Pad7)") (class "Default")
      (node (ref "EXP") (pin "7") (pinfunction "7_7") (pintype "passive"))
    )
    (net (code "108") (name "unconnected-(JTAG-Pad2)") (class "Default")
      (node (ref "JTAG") (pin "2") (pinfunction "2_2") (pintype "passive"))
    )
    (net (code "109") (name "unconnected-(JTAG-Pad11)") (class "Default")
      (node (ref "JTAG") (pin "11") (pinfunction "11_11") (pintype "passive"))
    )
    (net (code "110") (name "unconnected-(JTAG-Pad15)") (class "Default")
      (node (ref "JTAG") (pin "15") (pinfunction "15_15") (pintype "passive"))
    )
    (net (code "111") (name "unconnected-(JTAG-Pad17)") (class "Default")
      (node (ref "JTAG") (pin "17") (pinfunction "17_17") (pintype "passive"))
    )
    (net (code "112") (name "unconnected-(JTAG-Pad19)") (class "Default")
      (node (ref "JTAG") (pin "19") (pinfunction "19_19") (pintype "passive"))
    )
    (net (code "113") (name "unconnected-(OUT-Pad4)") (class "Default")
      (node (ref "OUT") (pin "4") (pinfunction "4_4") (pintype "passive"))
    )
    (net (code "114") (name "unconnected-(OUT-Pad5)") (class "Default")
      (node (ref "OUT") (pin "5") (pinfunction "5_5") (pintype "passive"))
    )
    (net (code "115") (name "unconnected-(POE-PG-Pad6)") (class "Default")
      (node (ref "POE") (pin "6") (pinfunction "PG_6") (pintype "output"))
    )
    (net (code "116") (name "unconnected-(SD-SW1-PadK1)") (class "Default")
      (node (ref "SD") (pin "K1") (pinfunction "SW1_K1") (pintype "bidirectional"))
    )
    (net (code "117") (name "unconnected-(SD-SW2-PadK2)") (class "Default")
      (node (ref "SD") (pin "K2") (pinfunction "SW2_K2") (pintype "bidirectional"))
    )
    (net (code "118") (name "unconnected-(USB-PadD+)") (class "Default")
      (node (ref "USB") (pin "D+") (pinfunction "D+_D+") (pintype "bidirectional"))
    )
    (net (code "119") (name "unconnected-(USB-PadD-)") (class "Default")
      (node (ref "USB") (pin "D-") (pinfunction "D-_D-") (pintype "bidirectional"))
    )
    (net (code "120") (name "unconnected-(VS-LINE2-Pad48)") (class "Default")
      (node (ref "VS") (pin "48") (pinfunction "LINE2_48") (pintype "passive"))
    )
    (net (code "121") (name "unconnected-(VS-MIC+{slash}LINE1-Pad1)") (class "Default")
      (node (ref "VS") (pin "1") (pinfunction "MIC+/LINE1_1") (pintype "passive"))
    )
    (net (code "122") (name "unconnected-(VS-MIC--Pad2)") (class "Default")
      (node (ref "VS") (pin "2") (pinfunction "MIC-_2") (pintype "passive"))
    )
    (net (code "123") (name "unconnected-(VS-TX-Pad27)") (class "Default")
      (node (ref "VS") (pin "27") (pinfunction "TX_27") (pintype "output"))
    )
    (net (code "124") (name "unconnected-(VS-VCO-Pad15)") (class "Default")
      (node (ref "VS") (pin "15") (pinfunction "VCO_15") (pintype "output"))
    )
  )
)
